# mc_pcb.net
KiCad netlist of a schematic drawn in EAGLE
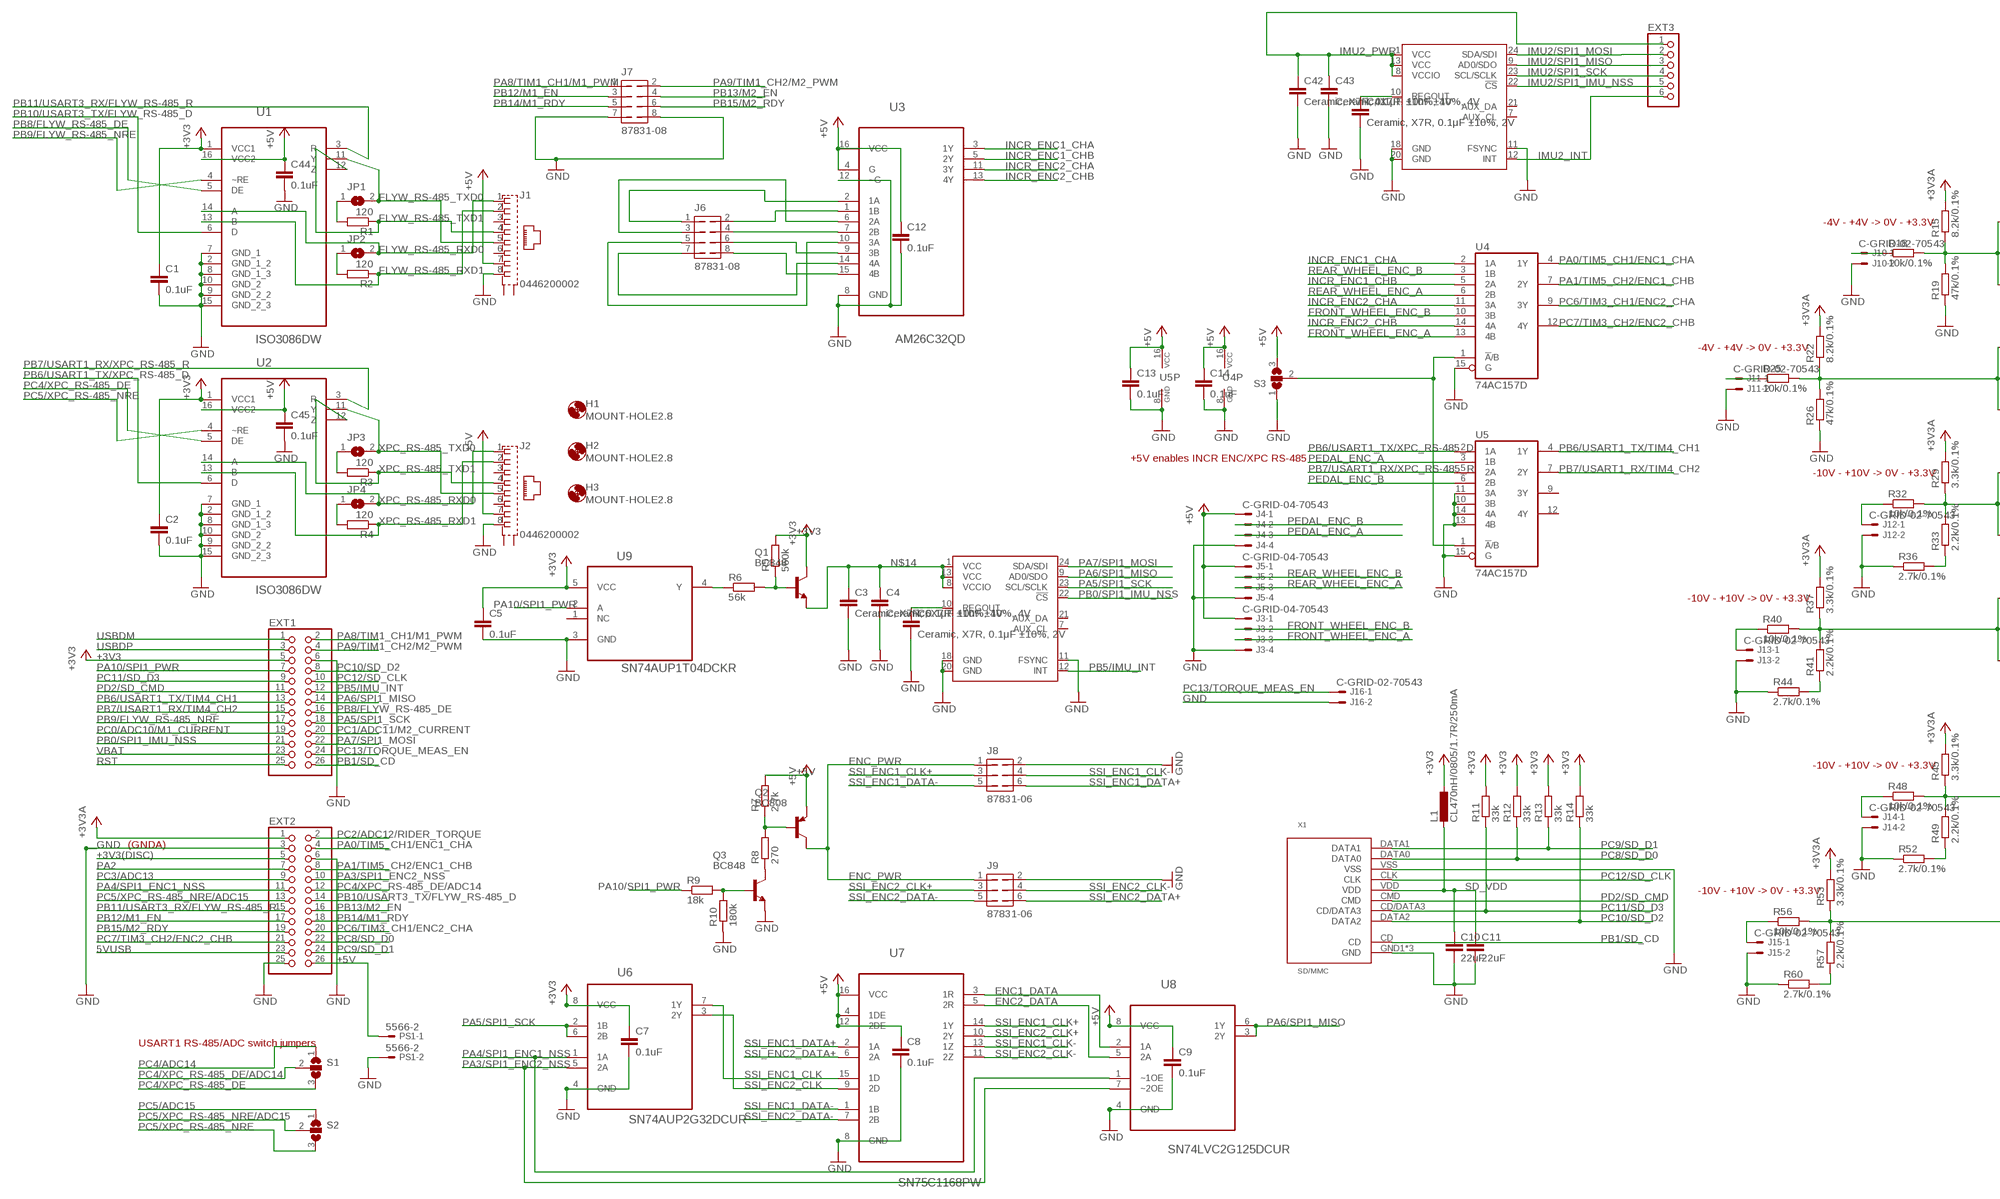
[diagram p0: schematic, sheet 1, part 1 of 2]
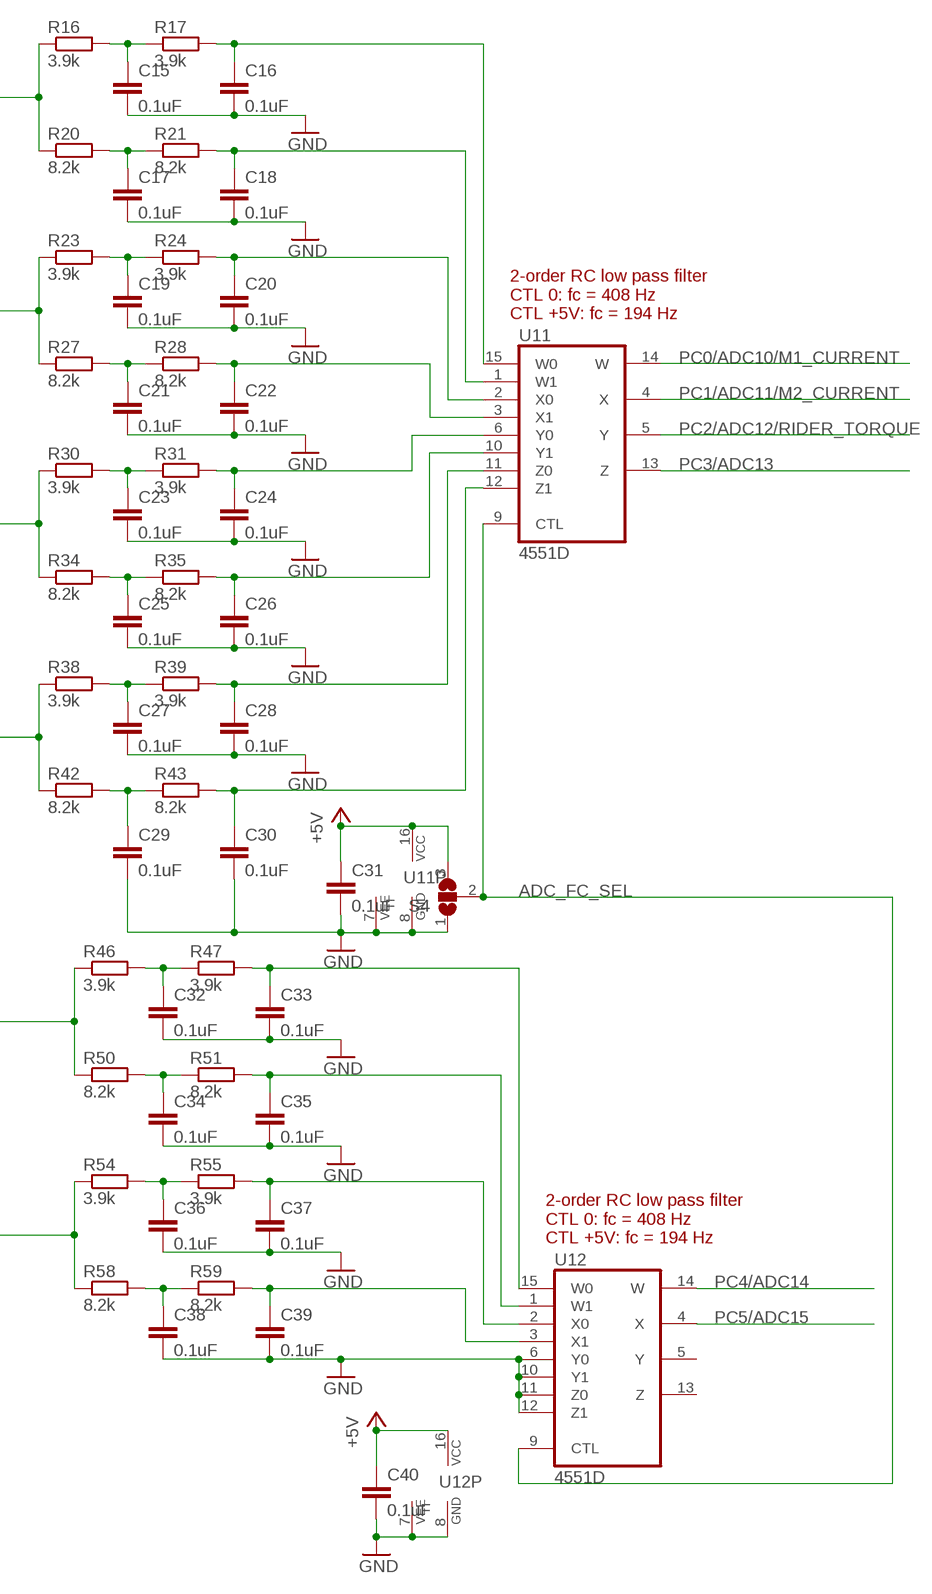
[diagram p1: schematic, sheet 1, part 2 of 2]

(export (version "E")
  (design (tool "Eeschema 10.0.6"))
  (components
    (comp (ref "C1")
      (value "0.1uF")
      (footprint "eagle-import:C0603")
      (libsource (lib "eagle-import") (part "C-EUC0603"))
    )
    (comp (ref "C2")
      (value "0.1uF")
      (footprint "eagle-import:C0603")
      (libsource (lib "eagle-import") (part "C-EUC0603"))
    )
    (comp (ref "C3")
      (value "Ceramic, X7R, 0.1μF ±10%, 4V")
      (footprint "eagle-import:C0603")
      (libsource (lib "eagle-import") (part "C-EUC0603"))
    )
    (comp (ref "C4")
      (value "Ceramic, X7R, 10nF ±10%, 4V")
      (footprint "eagle-import:C0603")
      (libsource (lib "eagle-import") (part "C-EUC0603"))
    )
    (comp (ref "C5")
      (value "0.1uF")
      (footprint "eagle-import:C0603")
      (libsource (lib "eagle-import") (part "C-EUC0603"))
    )
    (comp (ref "C6")
      (value "Ceramic, X7R, 0.1μF ±10%, 2V")
      (footprint "eagle-import:C0603")
      (libsource (lib "eagle-import") (part "C-EUC0603"))
    )
    (comp (ref "C7")
      (value "0.1uF")
      (footprint "eagle-import:C0603")
      (libsource (lib "eagle-import") (part "C-EUC0603"))
    )
    (comp (ref "C8")
      (value "0.1uF")
      (footprint "eagle-import:C0603")
      (libsource (lib "eagle-import") (part "C-EUC0603"))
    )
    (comp (ref "C9")
      (value "0.1uF")
      (footprint "eagle-import:C0603")
      (libsource (lib "eagle-import") (part "C-EUC0603"))
    )
    (comp (ref "C10")
      (value "22uF")
      (footprint "eagle-import:C0603")
      (libsource (lib "eagle-import") (part "C-EUC0603"))
    )
    (comp (ref "C11")
      (value "22uF")
      (footprint "eagle-import:C0603")
      (libsource (lib "eagle-import") (part "C-EUC0603"))
    )
    (comp (ref "C12")
      (value "0.1uF")
      (footprint "eagle-import:C0603")
      (libsource (lib "eagle-import") (part "C-EUC0603"))
    )
    (comp (ref "C13")
      (value "0.1uF")
      (footprint "eagle-import:C0603")
      (libsource (lib "eagle-import") (part "C-EUC0603"))
    )
    (comp (ref "C14")
      (value "0.1uF")
      (footprint "eagle-import:C0603")
      (libsource (lib "eagle-import") (part "C-EUC0603"))
    )
    (comp (ref "C15")
      (value "0.1uF")
      (footprint "eagle-import:C0603")
      (libsource (lib "eagle-import") (part "C-EUC0603"))
    )
    (comp (ref "C16")
      (value "0.1uF")
      (footprint "eagle-import:C0603")
      (libsource (lib "eagle-import") (part "C-EUC0603"))
    )
    (comp (ref "C17")
      (value "0.1uF")
      (footprint "eagle-import:C0603")
      (libsource (lib "eagle-import") (part "C-EUC0603"))
    )
    (comp (ref "C18")
      (value "0.1uF")
      (footprint "eagle-import:C0603")
      (libsource (lib "eagle-import") (part "C-EUC0603"))
    )
    (comp (ref "C19")
      (value "0.1uF")
      (footprint "eagle-import:C0603")
      (libsource (lib "eagle-import") (part "C-EUC0603"))
    )
    (comp (ref "C20")
      (value "0.1uF")
      (footprint "eagle-import:C0603")
      (libsource (lib "eagle-import") (part "C-EUC0603"))
    )
    (comp (ref "C21")
      (value "0.1uF")
      (footprint "eagle-import:C0603")
      (libsource (lib "eagle-import") (part "C-EUC0603"))
    )
    (comp (ref "C22")
      (value "0.1uF")
      (footprint "eagle-import:C0603")
      (libsource (lib "eagle-import") (part "C-EUC0603"))
    )
    (comp (ref "C23")
      (value "0.1uF")
      (footprint "eagle-import:C0603")
      (libsource (lib "eagle-import") (part "C-EUC0603"))
    )
    (comp (ref "C24")
      (value "0.1uF")
      (footprint "eagle-import:C0603")
      (libsource (lib "eagle-import") (part "C-EUC0603"))
    )
    (comp (ref "C25")
      (value "0.1uF")
      (footprint "eagle-import:C0603")
      (libsource (lib "eagle-import") (part "C-EUC0603"))
    )
    (comp (ref "C26")
      (value "0.1uF")
      (footprint "eagle-import:C0603")
      (libsource (lib "eagle-import") (part "C-EUC0603"))
    )
    (comp (ref "C27")
      (value "0.1uF")
      (footprint "eagle-import:C0603")
      (libsource (lib "eagle-import") (part "C-EUC0603"))
    )
    (comp (ref "C28")
      (value "0.1uF")
      (footprint "eagle-import:C0603")
      (libsource (lib "eagle-import") (part "C-EUC0603"))
    )
    (comp (ref "C29")
      (value "0.1uF")
      (footprint "eagle-import:C0603")
      (libsource (lib "eagle-import") (part "C-EUC0603"))
    )
    (comp (ref "C30")
      (value "0.1uF")
      (footprint "eagle-import:C0603")
      (libsource (lib "eagle-import") (part "C-EUC0603"))
    )
    (comp (ref "C31")
      (value "0.1uF")
      (footprint "eagle-import:C0603")
      (libsource (lib "eagle-import") (part "C-EUC0603"))
    )
    (comp (ref "C32")
      (value "0.1uF")
      (footprint "eagle-import:C0603")
      (libsource (lib "eagle-import") (part "C-EUC0603"))
    )
    (comp (ref "C33")
      (value "0.1uF")
      (footprint "eagle-import:C0603")
      (libsource (lib "eagle-import") (part "C-EUC0603"))
    )
    (comp (ref "C34")
      (value "0.1uF")
      (footprint "eagle-import:C0603")
      (libsource (lib "eagle-import") (part "C-EUC0603"))
    )
    (comp (ref "C35")
      (value "0.1uF")
      (footprint "eagle-import:C0603")
      (libsource (lib "eagle-import") (part "C-EUC0603"))
    )
    (comp (ref "C36")
      (value "0.1uF")
      (footprint "eagle-import:C0603")
      (libsource (lib "eagle-import") (part "C-EUC0603"))
    )
    (comp (ref "C37")
      (value "0.1uF")
      (footprint "eagle-import:C0603")
      (libsource (lib "eagle-import") (part "C-EUC0603"))
    )
    (comp (ref "C38")
      (value "0.1uF")
      (footprint "eagle-import:C0603")
      (libsource (lib "eagle-import") (part "C-EUC0603"))
    )
    (comp (ref "C39")
      (value "0.1uF")
      (footprint "eagle-import:C0603")
      (libsource (lib "eagle-import") (part "C-EUC0603"))
    )
    (comp (ref "C40")
      (value "0.1uF")
      (footprint "eagle-import:C0603")
      (libsource (lib "eagle-import") (part "C-EUC0603"))
    )
    (comp (ref "C41")
      (value "Ceramic, X7R, 0.1μF ±10%, 2V")
      (footprint "eagle-import:C0603")
      (libsource (lib "eagle-import") (part "C-EUC0603"))
    )
    (comp (ref "C42")
      (value "Ceramic, X7R, 0.1μF ±10%, 4V")
      (footprint "eagle-import:C0603")
      (libsource (lib "eagle-import") (part "C-EUC0603"))
    )
    (comp (ref "C43")
      (value "Ceramic, X7R, 10nF ±10%, 4V")
      (footprint "eagle-import:C0603")
      (libsource (lib "eagle-import") (part "C-EUC0603"))
    )
    (comp (ref "C44")
      (value "0.1uF")
      (footprint "eagle-import:C0603")
      (libsource (lib "eagle-import") (part "C-EUC0603"))
    )
    (comp (ref "C45")
      (value "0.1uF")
      (footprint "eagle-import:C0603")
      (libsource (lib "eagle-import") (part "C-EUC0603"))
    )
    (comp (ref "EXT1")
      (value "PINHD-2X13")
      (footprint "eagle-import:2X13")
      (libsource (lib "eagle-import") (part "PINHD-2X13"))
    )
    (comp (ref "EXT2")
      (value "PINHD-2X13")
      (footprint "eagle-import:2X13")
      (libsource (lib "eagle-import") (part "PINHD-2X13"))
    )
    (comp (ref "EXT3")
      (value "PINHD-1X6")
      (footprint "eagle-import:1X06")
      (libsource (lib "eagle-import") (part "PINHD-1X6"))
    )
    (comp (ref "H1")
      (value "MOUNT-HOLE2.8")
      (footprint "eagle-import:2,8")
      (libsource (lib "eagle-import") (part "MOUNT-HOLE2.8"))
    )
    (comp (ref "H2")
      (value "MOUNT-HOLE2.8")
      (footprint "eagle-import:2,8")
      (libsource (lib "eagle-import") (part "MOUNT-HOLE2.8"))
    )
    (comp (ref "H3")
      (value "MOUNT-HOLE2.8")
      (footprint "eagle-import:2,8")
      (libsource (lib "eagle-import") (part "MOUNT-HOLE2.8"))
    )
    (comp (ref "J1")
      (value "0446200002")
      (footprint "eagle-import:0446200002")
      (fields (field (name "MF") "MOLEX"))
      (libsource (lib "eagle-import") (part "0446200002"))
    )
    (comp (ref "J2")
      (value "0446200002")
      (footprint "eagle-import:0446200002")
      (fields (field (name "MF") "MOLEX"))
      (libsource (lib "eagle-import") (part "0446200002"))
    )
    (comp (ref "J3")
      (value "C-GRID-04-70543")
      (footprint "eagle-import:70543-04")
      (libsource (lib "eagle-import") (part "C-GRID-04-70543"))
    )
    (comp (ref "J4")
      (value "C-GRID-04-70543")
      (footprint "eagle-import:70543-04")
      (libsource (lib "eagle-import") (part "C-GRID-04-70543"))
    )
    (comp (ref "J5")
      (value "C-GRID-04-70543")
      (footprint "eagle-import:70543-04")
      (libsource (lib "eagle-import") (part "C-GRID-04-70543"))
    )
    (comp (ref "J6")
      (value "87831-08")
      (footprint "eagle-import:87831-08")
      (libsource (lib "eagle-import") (part "87831-08"))
    )
    (comp (ref "J7")
      (value "87831-08")
      (footprint "eagle-import:87831-08")
      (libsource (lib "eagle-import") (part "87831-08"))
    )
    (comp (ref "J8")
      (value "87831-06")
      (footprint "eagle-import:87831-06")
      (libsource (lib "eagle-import") (part "87831-06"))
    )
    (comp (ref "J9")
      (value "87831-06")
      (footprint "eagle-import:87831-06")
      (libsource (lib "eagle-import") (part "87831-06"))
    )
    (comp (ref "J10")
      (value "C-GRID-02-70543")
      (footprint "eagle-import:70543-02")
      (libsource (lib "eagle-import") (part "C-GRID-02-70543"))
    )
    (comp (ref "J11")
      (value "C-GRID-02-70543")
      (footprint "eagle-import:70543-02")
      (libsource (lib "eagle-import") (part "C-GRID-02-70543"))
    )
    (comp (ref "J12")
      (value "C-GRID-02-70543")
      (footprint "eagle-import:70543-02")
      (libsource (lib "eagle-import") (part "C-GRID-02-70543"))
    )
    (comp (ref "J13")
      (value "C-GRID-02-70543")
      (footprint "eagle-import:70543-02")
      (libsource (lib "eagle-import") (part "C-GRID-02-70543"))
    )
    (comp (ref "J14")
      (value "C-GRID-02-70543")
      (footprint "eagle-import:70543-02")
      (libsource (lib "eagle-import") (part "C-GRID-02-70543"))
    )
    (comp (ref "J15")
      (value "C-GRID-02-70543")
      (footprint "eagle-import:70543-02")
      (libsource (lib "eagle-import") (part "C-GRID-02-70543"))
    )
    (comp (ref "J16")
      (value "C-GRID-02-70543")
      (footprint "eagle-import:70543-02")
      (libsource (lib "eagle-import") (part "C-GRID-02-70543"))
    )
    (comp (ref "JP1") (value "SJ") (footprint "eagle-import:SJ") (libsource (lib "eagle-import") (part "SJ")))
    (comp (ref "JP2") (value "SJ") (footprint "eagle-import:SJ") (libsource (lib "eagle-import") (part "SJ")))
    (comp (ref "JP3") (value "SJ") (footprint "eagle-import:SJ") (libsource (lib "eagle-import") (part "SJ")))
    (comp (ref "JP4") (value "SJ") (footprint "eagle-import:SJ") (libsource (lib "eagle-import") (part "SJ")))
    (comp (ref "L1")
      (value "CL470nH/0805/1.7R/250mA")
      (footprint "eagle-import:L2012C")
      (libsource (lib "eagle-import") (part "L-EUL2012C"))
    )
    (comp (ref "PS1")
      (value "5566-2")
      (footprint "eagle-import:5566-2")
      (libsource (lib "eagle-import") (part "5566-2"))
    )
    (comp (ref "Q1")
      (value "BC848")
      (footprint "eagle-import:SOT23")
      (libsource (lib "eagle-import") (part "BC848"))
    )
    (comp (ref "Q2")
      (value "BC808")
      (footprint "eagle-import:SOT23-BEC")
      (libsource (lib "eagle-import") (part "-PNP-SOT23-BECBC808-16"))
    )
    (comp (ref "Q3")
      (value "BC848")
      (footprint "eagle-import:SOT23")
      (libsource (lib "eagle-import") (part "BC848"))
    )
    (comp (ref "R1")
      (value "120")
      (footprint "eagle-import:R0603")
      (libsource (lib "eagle-import") (part "R-EU_R0603"))
    )
    (comp (ref "R2")
      (value "120")
      (footprint "eagle-import:R0603")
      (libsource (lib "eagle-import") (part "R-EU_R0603"))
    )
    (comp (ref "R3")
      (value "120")
      (footprint "eagle-import:R0603")
      (libsource (lib "eagle-import") (part "R-EU_R0603"))
    )
    (comp (ref "R4")
      (value "120")
      (footprint "eagle-import:R0603")
      (libsource (lib "eagle-import") (part "R-EU_R0603"))
    )
    (comp (ref "R5")
      (value "560k")
      (footprint "eagle-import:R0603")
      (libsource (lib "eagle-import") (part "R-EU_R0603"))
    )
    (comp (ref "R6")
      (value "56k")
      (footprint "eagle-import:R0603")
      (libsource (lib "eagle-import") (part "R-EU_R0603"))
    )
    (comp (ref "R7")
      (value "2.7k")
      (footprint "eagle-import:R1210")
      (libsource (lib "eagle-import") (part "R-EU_R1210"))
    )
    (comp (ref "R8")
      (value "270")
      (footprint "eagle-import:R1210")
      (libsource (lib "eagle-import") (part "R-EU_R1210"))
    )
    (comp (ref "R9")
      (value "18k")
      (footprint "eagle-import:R0603")
      (libsource (lib "eagle-import") (part "R-EU_R0603"))
    )
    (comp (ref "R10")
      (value "180k")
      (footprint "eagle-import:R0603")
      (libsource (lib "eagle-import") (part "R-EU_R0603"))
    )
    (comp (ref "R11")
      (value "33k")
      (footprint "eagle-import:R0603")
      (libsource (lib "eagle-import") (part "R-EU_R0603"))
    )
    (comp (ref "R12")
      (value "33k")
      (footprint "eagle-import:R0603")
      (libsource (lib "eagle-import") (part "R-EU_R0603"))
    )
    (comp (ref "R13")
      (value "33k")
      (footprint "eagle-import:R0603")
      (libsource (lib "eagle-import") (part "R-EU_R0603"))
    )
    (comp (ref "R14")
      (value "33k")
      (footprint "eagle-import:R0603")
      (libsource (lib "eagle-import") (part "R-EU_R0603"))
    )
    (comp (ref "R15")
      (value "8.2k/0.1%")
      (footprint "eagle-import:R0603")
      (libsource (lib "eagle-import") (part "R-EU_R0603"))
    )
    (comp (ref "R16")
      (value "3.9k")
      (footprint "eagle-import:R0603")
      (libsource (lib "eagle-import") (part "R-EU_R0603"))
    )
    (comp (ref "R17")
      (value "3.9k")
      (footprint "eagle-import:R0603")
      (libsource (lib "eagle-import") (part "R-EU_R0603"))
    )
    (comp (ref "R18")
      (value "10k/0.1%")
      (footprint "eagle-import:R0603")
      (libsource (lib "eagle-import") (part "R-EU_R0603"))
    )
    (comp (ref "R19")
      (value "47k/0.1%")
      (footprint "eagle-import:R0603")
      (libsource (lib "eagle-import") (part "R-EU_R0603"))
    )
    (comp (ref "R20")
      (value "8.2k")
      (footprint "eagle-import:R0603")
      (libsource (lib "eagle-import") (part "R-EU_R0603"))
    )
    (comp (ref "R21")
      (value "8.2k")
      (footprint "eagle-import:R0603")
      (libsource (lib "eagle-import") (part "R-EU_R0603"))
    )
    (comp (ref "R22")
      (value "8.2k/0.1%")
      (footprint "eagle-import:R0603")
      (libsource (lib "eagle-import") (part "R-EU_R0603"))
    )
    (comp (ref "R23")
      (value "3.9k")
      (footprint "eagle-import:R0603")
      (libsource (lib "eagle-import") (part "R-EU_R0603"))
    )
    (comp (ref "R24")
      (value "3.9k")
      (footprint "eagle-import:R0603")
      (libsource (lib "eagle-import") (part "R-EU_R0603"))
    )
    (comp (ref "R25")
      (value "10k/0.1%")
      (footprint "eagle-import:R0603")
      (libsource (lib "eagle-import") (part "R-EU_R0603"))
    )
    (comp (ref "R26")
      (value "47k/0.1%")
      (footprint "eagle-import:R0603")
      (libsource (lib "eagle-import") (part "R-EU_R0603"))
    )
    (comp (ref "R27")
      (value "8.2k")
      (footprint "eagle-import:R0603")
      (libsource (lib "eagle-import") (part "R-EU_R0603"))
    )
    (comp (ref "R28")
      (value "8.2k")
      (footprint "eagle-import:R0603")
      (libsource (lib "eagle-import") (part "R-EU_R0603"))
    )
    (comp (ref "R29")
      (value "3.3k/0.1%")
      (footprint "eagle-import:R0603")
      (libsource (lib "eagle-import") (part "R-EU_R0603"))
    )
    (comp (ref "R30")
      (value "3.9k")
      (footprint "eagle-import:R0603")
      (libsource (lib "eagle-import") (part "R-EU_R0603"))
    )
    (comp (ref "R31")
      (value "3.9k")
      (footprint "eagle-import:R0603")
      (libsource (lib "eagle-import") (part "R-EU_R0603"))
    )
    (comp (ref "R32")
      (value "10k/0.1%")
      (footprint "eagle-import:R0603")
      (libsource (lib "eagle-import") (part "R-EU_R0603"))
    )
    (comp (ref "R33")
      (value "2.2k/0.1%")
      (footprint "eagle-import:R0603")
      (libsource (lib "eagle-import") (part "R-EU_R0603"))
    )
    (comp (ref "R34")
      (value "8.2k")
      (footprint "eagle-import:R0603")
      (libsource (lib "eagle-import") (part "R-EU_R0603"))
    )
    (comp (ref "R35")
      (value "8.2k")
      (footprint "eagle-import:R0603")
      (libsource (lib "eagle-import") (part "R-EU_R0603"))
    )
    (comp (ref "R36")
      (value "2.7k/0.1%")
      (footprint "eagle-import:R0603")
      (libsource (lib "eagle-import") (part "R-EU_R0603"))
    )
    (comp (ref "R37")
      (value "3.3k/0.1%")
      (footprint "eagle-import:R0603")
      (libsource (lib "eagle-import") (part "R-EU_R0603"))
    )
    (comp (ref "R38")
      (value "3.9k")
      (footprint "eagle-import:R0603")
      (libsource (lib "eagle-import") (part "R-EU_R0603"))
    )
    (comp (ref "R39")
      (value "3.9k")
      (footprint "eagle-import:R0603")
      (libsource (lib "eagle-import") (part "R-EU_R0603"))
    )
    (comp (ref "R40")
      (value "10k/0.1%")
      (footprint "eagle-import:R0603")
      (libsource (lib "eagle-import") (part "R-EU_R0603"))
    )
    (comp (ref "R41")
      (value "2.2k/0.1%")
      (footprint "eagle-import:R0603")
      (libsource (lib "eagle-import") (part "R-EU_R0603"))
    )
    (comp (ref "R42")
      (value "8.2k")
      (footprint "eagle-import:R0603")
      (libsource (lib "eagle-import") (part "R-EU_R0603"))
    )
    (comp (ref "R43")
      (value "8.2k")
      (footprint "eagle-import:R0603")
      (libsource (lib "eagle-import") (part "R-EU_R0603"))
    )
    (comp (ref "R44")
      (value "2.7k/0.1%")
      (footprint "eagle-import:R0603")
      (libsource (lib "eagle-import") (part "R-EU_R0603"))
    )
    (comp (ref "R45")
      (value "3.3k/0.1%")
      (footprint "eagle-import:R0603")
      (libsource (lib "eagle-import") (part "R-EU_R0603"))
    )
    (comp (ref "R46")
      (value "3.9k")
      (footprint "eagle-import:R0603")
      (libsource (lib "eagle-import") (part "R-EU_R0603"))
    )
    (comp (ref "R47")
      (value "3.9k")
      (footprint "eagle-import:R0603")
      (libsource (lib "eagle-import") (part "R-EU_R0603"))
    )
    (comp (ref "R48")
      (value "10k/0.1%")
      (footprint "eagle-import:R0603")
      (libsource (lib "eagle-import") (part "R-EU_R0603"))
    )
    (comp (ref "R49")
      (value "2.2k/0.1%")
      (footprint "eagle-import:R0603")
      (libsource (lib "eagle-import") (part "R-EU_R0603"))
    )
    (comp (ref "R50")
      (value "8.2k")
      (footprint "eagle-import:R0603")
      (libsource (lib "eagle-import") (part "R-EU_R0603"))
    )
    (comp (ref "R51")
      (value "8.2k")
      (footprint "eagle-import:R0603")
      (libsource (lib "eagle-import") (part "R-EU_R0603"))
    )
    (comp (ref "R52")
      (value "2.7k/0.1%")
      (footprint "eagle-import:R0603")
      (libsource (lib "eagle-import") (part "R-EU_R0603"))
    )
    (comp (ref "R53")
      (value "3.3k/0.1%")
      (footprint "eagle-import:R0603")
      (libsource (lib "eagle-import") (part "R-EU_R0603"))
    )
    (comp (ref "R54")
      (value "3.9k")
      (footprint "eagle-import:R0603")
      (libsource (lib "eagle-import") (part "R-EU_R0603"))
    )
    (comp (ref "R55")
      (value "3.9k")
      (footprint "eagle-import:R0603")
      (libsource (lib "eagle-import") (part "R-EU_R0603"))
    )
    (comp (ref "R56")
      (value "10k/0.1%")
      (footprint "eagle-import:R0603")
      (libsource (lib "eagle-import") (part "R-EU_R0603"))
    )
    (comp (ref "R57")
      (value "2.2k/0.1%")
      (footprint "eagle-import:R0603")
      (libsource (lib "eagle-import") (part "R-EU_R0603"))
    )
    (comp (ref "R58")
      (value "8.2k")
      (footprint "eagle-import:R0603")
      (libsource (lib "eagle-import") (part "R-EU_R0603"))
    )
    (comp (ref "R59")
      (value "8.2k")
      (footprint "eagle-import:R0603")
      (libsource (lib "eagle-import") (part "R-EU_R0603"))
    )
    (comp (ref "R60")
      (value "2.7k/0.1%")
      (footprint "eagle-import:R0603")
      (libsource (lib "eagle-import") (part "R-EU_R0603"))
    )
    (comp (ref "S1")
      (value "SJ2W")
      (footprint "eagle-import:SJ_2")
      (libsource (lib "eagle-import") (part "SJ2W"))
    )
    (comp (ref "S2")
      (value "SJ2W")
      (footprint "eagle-import:SJ_2")
      (libsource (lib "eagle-import") (part "SJ2W"))
    )
    (comp (ref "S3")
      (value "SJ2W")
      (footprint "eagle-import:SJ_2")
      (libsource (lib "eagle-import") (part "SJ2W"))
    )
    (comp (ref "S4")
      (value "SJ2W")
      (footprint "eagle-import:SJ_2")
      (libsource (lib "eagle-import") (part "SJ2W"))
    )
    (comp (ref "U1")
      (value "ISO3086DW")
      (footprint "eagle-import:SOIC127P1030X265-16N")
      (fields (field (name "MPN") "ISO3080DW"))
      (libsource (lib "eagle-import") (part "ISO3086DW"))
    )
    (comp (ref "U2")
      (value "ISO3086DW")
      (footprint "eagle-import:SOIC127P1030X265-16N")
      (fields (field (name "MPN") "ISO3080DW"))
      (libsource (lib "eagle-import") (part "ISO3086DW"))
    )
    (comp (ref "U3")
      (value "AM26C32QD")
      (footprint "eagle-import:SOIC127P600X175-16N")
      (libsource (lib "eagle-import") (part "AM26C32QD"))
    )
    (comp (ref "U4")
      (value "74AC157D")
      (footprint "eagle-import:SO16")
      (libsource (lib "eagle-import") (part "74157DAC"))
    )
    (comp (ref "U5")
      (value "74AC157D")
      (footprint "eagle-import:SO16")
      (libsource (lib "eagle-import") (part "74157DAC"))
    )
    (comp (ref "U6")
      (value "SN74AUP2G32DCUR")
      (footprint "eagle-import:SOP50P310X90-8N")
      (libsource (lib "eagle-import") (part "SN74AUP2G32DCUR"))
    )
    (comp (ref "U7")
      (value "SN75C1168PW")
      (footprint "eagle-import:SOP65P640X120-16N")
      (libsource (lib "eagle-import") (part "SN75C1168PW"))
    )
    (comp (ref "U8")
      (value "SN74LVC2G125DCUR")
      (footprint "eagle-import:SOP50P310X90-8N")
      (libsource (lib "eagle-import") (part "SN74LVC2G125DCUR"))
    )
    (comp (ref "U9")
      (value "SN74AUP1T04DCKR")
      (footprint "eagle-import:SOT65P210X110-5N")
      (libsource (lib "eagle-import") (part "SN74AUP1T04DCKR"))
    )
    (comp (ref "U10")
      (value "MPU-9250")
      (footprint "eagle-import:QFN24-SMALL")
      (libsource (lib "eagle-import") (part "MPU-9250"))
    )
    (comp (ref "U11")
      (value "4551D")
      (footprint "eagle-import:SO16")
      (libsource (lib "eagle-import") (part "4551D"))
    )
    (comp (ref "U12")
      (value "4551D")
      (footprint "eagle-import:SO16")
      (libsource (lib "eagle-import") (part "4551D"))
    )
    (comp (ref "U13")
      (value "MPU-9250")
      (footprint "eagle-import:QFN24-SMALL")
      (libsource (lib "eagle-import") (part "MPU-9250"))
    )
    (comp (ref "X1")
      (value "10100660")
      (footprint "eagle-import:-68-6")
      (libsource (lib "eagle-import") (part "10100660"))
    )
  )
  (nets
    (net (code "1") (name "+3V3") (class "Default")
      (node (ref "C1") (pin "1") (pinfunction "1_1") (pintype "passive"))
      (node (ref "C2") (pin "1") (pinfunction "1_1") (pintype "passive"))
      (node (ref "C5") (pin "1") (pinfunction "1_1") (pintype "passive"))
      (node (ref "C7") (pin "1") (pinfunction "1_1") (pintype "passive"))
      (node (ref "EXT1") (pin "5") (pinfunction "5_5") (pintype "passive"))
      (node (ref "L1") (pin "1") (pinfunction "1_1") (pintype "passive"))
      (node (ref "Q1") (pin "3") (pinfunction "C_3") (pintype "passive"))
      (node (ref "R11") (pin "2") (pinfunction "2_2") (pintype "passive"))
      (node (ref "R12") (pin "2") (pinfunction "2_2") (pintype "passive"))
      (node (ref "R13") (pin "2") (pinfunction "2_2") (pintype "passive"))
      (node (ref "R14") (pin "2") (pinfunction "2_2") (pintype "passive"))
      (node (ref "R5") (pin "2") (pinfunction "2_2") (pintype "passive"))
      (node (ref "U1") (pin "1") (pinfunction "VCC1_1") (pintype "power_in"))
      (node (ref "U2") (pin "1") (pinfunction "VCC1_1") (pintype "power_in"))
      (node (ref "U6") (pin "8") (pinfunction "VCC_8") (pintype "power_in"))
      (node (ref "U9") (pin "5") (pinfunction "VCC_5") (pintype "power_in"))
    )
    (net (code "2") (name "+3V3A") (class "Default")
      (node (ref "EXT2") (pin "1") (pinfunction "1_1") (pintype "passive"))
      (node (ref "R15") (pin "2") (pinfunction "2_2") (pintype "passive"))
      (node (ref "R22") (pin "2") (pinfunction "2_2") (pintype "passive"))
      (node (ref "R29") (pin "2") (pinfunction "2_2") (pintype "passive"))
      (node (ref "R37") (pin "2") (pinfunction "2_2") (pintype "passive"))
      (node (ref "R45") (pin "2") (pinfunction "2_2") (pintype "passive"))
      (node (ref "R53") (pin "2") (pinfunction "2_2") (pintype "passive"))
    )
    (net (code "3") (name "+5V") (class "Default")
      (node (ref "C12") (pin "1") (pinfunction "1_1") (pintype "passive"))
      (node (ref "C13") (pin "1") (pinfunction "1_1") (pintype "passive"))
      (node (ref "C14") (pin "1") (pinfunction "1_1") (pintype "passive"))
      (node (ref "C31") (pin "1") (pinfunction "1_1") (pintype "passive"))
      (node (ref "C40") (pin "1") (pinfunction "1_1") (pintype "passive"))
      (node (ref "C44") (pin "1") (pinfunction "1_1") (pintype "passive"))
      (node (ref "C45") (pin "1") (pinfunction "1_1") (pintype "passive"))
      (node (ref "C8") (pin "1") (pinfunction "1_1") (pintype "passive"))
      (node (ref "C9") (pin "1") (pinfunction "1_1") (pintype "passive"))
      (node (ref "EXT2") (pin "26") (pinfunction "26_26") (pintype "passive"))
      (node (ref "J1") (pin "7") (pinfunction "7_7") (pintype "passive"))
      (node (ref "J2") (pin "7") (pinfunction "7_7") (pintype "passive"))
      (node (ref "J3") (pin "1") (pinfunction "S_1") (pintype "passive"))
      (node (ref "J4") (pin "1") (pinfunction "S_1") (pintype "passive"))
      (node (ref "J5") (pin "1") (pinfunction "S_1") (pintype "passive"))
      (node (ref "PS1") (pin "1") (pinfunction "S_1") (pintype "passive"))
      (node (ref "Q2") (pin "E") (pinfunction "E_E") (pintype "passive"))
      (node (ref "R7") (pin "2") (pinfunction "2_2") (pintype "passive"))
      (node (ref "S3") (pin "3") (pinfunction "3_3") (pintype "passive"))
      (node (ref "S4") (pin "3") (pinfunction "3_3") (pintype "passive"))
      (node (ref "U1") (pin "16") (pinfunction "VCC2_16") (pintype "power_in"))
      (node (ref "U11") (pin "16") (pinfunction "VCC_16") (pintype "power_in"))
      (node (ref "U12") (pin "16") (pinfunction "VCC_16") (pintype "power_in"))
      (node (ref "U2") (pin "16") (pinfunction "VCC2_16") (pintype "power_in"))
      (node (ref "U3") (pin "16") (pinfunction "VCC_16") (pintype "power_in"))
      (node (ref "U3") (pin "4") (pinfunction "G_4") (pintype "input"))
      (node (ref "U4") (pin "16") (pinfunction "VCC_16") (pintype "power_in"))
      (node (ref "U5") (pin "16") (pinfunction "VCC_16") (pintype "power_in"))
      (node (ref "U7") (pin "12") (pinfunction "2DE_12") (pintype "input"))
      (node (ref "U7") (pin "16") (pinfunction "VCC_16") (pintype "power_in"))
      (node (ref "U7") (pin "4") (pinfunction "1DE_4") (pintype "input"))
      (node (ref "U8") (pin "8") (pinfunction "VCC_8") (pintype "power_in"))
    )
    (net (code "4") (name "/+3V3(DISC)") (class "Default")
      (node (ref "EXT2") (pin "5") (pinfunction "5_5") (pintype "passive"))
    )
    (net (code "5") (name "/5VUSB") (class "Default")
      (node (ref "EXT2") (pin "23") (pinfunction "23_23") (pintype "passive"))
    )
    (net (code "6") (name "/ADC_FC_SEL") (class "Default")
      (node (ref "S4") (pin "2") (pinfunction "2_2") (pintype "passive"))
      (node (ref "U11") (pin "9") (pinfunction "CTL_9") (pintype "input"))
      (node (ref "U12") (pin "9") (pinfunction "CTL_9") (pintype "input"))
    )
    (net (code "7") (name "/ENC1_DATA") (class "Default")
      (node (ref "U7") (pin "3") (pinfunction "1R_3") (pintype "output"))
      (node (ref "U8") (pin "2") (pinfunction "1A_2") (pintype "input"))
    )
    (net (code "8") (name "/ENC2_DATA") (class "Default")
      (node (ref "U7") (pin "5") (pinfunction "2R_5") (pintype "output"))
      (node (ref "U8") (pin "5") (pinfunction "2A_5") (pintype "input"))
    )
    (net (code "9") (name "/ENC_PWR") (class "Default")
      (node (ref "J8") (pin "1") (pinfunction "1_1") (pintype "passive"))
      (node (ref "J9") (pin "1") (pinfunction "1_1") (pintype "passive"))
      (node (ref "Q2") (pin "C") (pinfunction "C_C") (pintype "passive"))
    )
    (net (code "10") (name "/FLYW_RS-485_RXD0") (class "Default")
      (node (ref "J1") (pin "1") (pinfunction "1_1") (pintype "passive"))
      (node (ref "JP2") (pin "2") (pinfunction "2_2") (pintype "passive"))
      (node (ref "U1") (pin "14") (pinfunction "A_14") (pintype "input"))
    )
    (net (code "11") (name "/FLYW_RS-485_RXD1") (class "Default")
      (node (ref "J1") (pin "2") (pinfunction "2_2") (pintype "passive"))
      (node (ref "R2") (pin "1") (pinfunction "1_1") (pintype "passive"))
      (node (ref "U1") (pin "13") (pinfunction "B_13") (pintype "input"))
    )
    (net (code "12") (name "/FLYW_RS-485_TXD0") (class "Default")
      (node (ref "J1") (pin "5") (pinfunction "5_5") (pintype "passive"))
      (node (ref "JP1") (pin "2") (pinfunction "2_2") (pintype "passive"))
      (node (ref "U1") (pin "11") (pinfunction "Y_11") (pintype "output"))
    )
    (net (code "13") (name "/FLYW_RS-485_TXD1") (class "Default")
      (node (ref "J1") (pin "4") (pinfunction "4_4") (pintype "passive"))
      (node (ref "R1") (pin "1") (pinfunction "1_1") (pintype "passive"))
      (node (ref "U1") (pin "12") (pinfunction "Z_12") (pintype "output"))
    )
    (net (code "14") (name "/FRONT_WHEEL_ENC_A") (class "Default")
      (node (ref "J3") (pin "3") (pinfunction "S_3") (pintype "passive"))
      (node (ref "U4") (pin "13") (pinfunction "4B_13") (pintype "input"))
    )
    (net (code "15") (name "/FRONT_WHEEL_ENC_B") (class "Default")
      (node (ref "J3") (pin "2") (pinfunction "S_2") (pintype "passive"))
      (node (ref "U4") (pin "10") (pinfunction "3B_10") (pintype "input"))
    )
    (net (code "16") (name "/IMU2_INT") (class "Default")
      (node (ref "EXT3") (pin "6") (pinfunction "6_6") (pintype "passive"))
      (node (ref "U13") (pin "12") (pinfunction "INT_12") (pintype "output"))
    )
    (net (code "17") (name "/IMU2_PWR") (class "Default")
      (node (ref "C42") (pin "1") (pinfunction "1_1") (pintype "passive"))
      (node (ref "C43") (pin "1") (pinfunction "1_1") (pintype "passive"))
      (node (ref "EXT3") (pin "1") (pinfunction "1_1") (pintype "passive"))
      (node (ref "U13") (pin "1") (pinfunction "VCC_1") (pintype "power_in"))
      (node (ref "U13") (pin "13") (pinfunction "VCC_13") (pintype "power_in"))
      (node (ref "U13") (pin "8") (pinfunction "VCCIO_8") (pintype "power_in"))
    )
    (net (code "18") (name "/IMU2{slash}SPI1_IMU_NSS") (class "Default")
      (node (ref "EXT3") (pin "5") (pinfunction "5_5") (pintype "passive"))
      (node (ref "U13") (pin "22") (pinfunction "~{CS}_22") (pintype "input"))
    )
    (net (code "19") (name "/IMU2{slash}SPI1_MISO") (class "Default")
      (node (ref "EXT3") (pin "3") (pinfunction "3_3") (pintype "passive"))
      (node (ref "U13") (pin "9") (pinfunction "AD0/SDO_9") (pintype "input"))
    )
    (net (code "20") (name "/IMU2{slash}SPI1_MOSI") (class "Default")
      (node (ref "EXT3") (pin "2") (pinfunction "2_2") (pintype "passive"))
      (node (ref "U13") (pin "24") (pinfunction "SDA/SDI_24") (pintype "output"))
    )
    (net (code "21") (name "/IMU2{slash}SPI1_SCK") (class "Default")
      (node (ref "EXT3") (pin "4") (pinfunction "4_4") (pintype "passive"))
      (node (ref "U13") (pin "23") (pinfunction "SCL/SCLK_23") (pintype "bidirectional"))
    )
    (net (code "22") (name "/INCR_ENC1_CHA") (class "Default")
      (node (ref "U3") (pin "3") (pinfunction "1Y_3") (pintype "output"))
      (node (ref "U4") (pin "2") (pinfunction "1A_2") (pintype "input"))
    )
    (net (code "23") (name "/INCR_ENC1_CHB") (class "Default")
      (node (ref "U3") (pin "5") (pinfunction "2Y_5") (pintype "output"))
      (node (ref "U4") (pin "5") (pinfunction "2A_5") (pintype "input"))
    )
    (net (code "24") (name "/INCR_ENC2_CHA") (class "Default")
      (node (ref "U3") (pin "11") (pinfunction "3Y_11") (pintype "output"))
      (node (ref "U4") (pin "11") (pinfunction "3A_11") (pintype "input"))
    )
    (net (code "25") (name "/INCR_ENC2_CHB") (class "Default")
      (node (ref "U3") (pin "13") (pinfunction "4Y_13") (pintype "output"))
      (node (ref "U4") (pin "14") (pinfunction "4A_14") (pintype "input"))
    )
    (net (code "26") (name "/N$14") (class "Default")
      (node (ref "C3") (pin "1") (pinfunction "1_1") (pintype "passive"))
      (node (ref "C4") (pin "1") (pinfunction "1_1") (pintype "passive"))
      (node (ref "Q1") (pin "2") (pinfunction "E_2") (pintype "passive"))
      (node (ref "U10") (pin "1") (pinfunction "VCC_1") (pintype "power_in"))
      (node (ref "U10") (pin "13") (pinfunction "VCC_13") (pintype "power_in"))
      (node (ref "U10") (pin "8") (pinfunction "VCCIO_8") (pintype "power_in"))
    )
    (net (code "27") (name "/PA0{slash}TIM5_CH1{slash}ENC1_CHA") (class "Default")
      (node (ref "EXT2") (pin "4") (pinfunction "4_4") (pintype "passive"))
      (node (ref "U4") (pin "4") (pinfunction "1Y_4") (pintype "output"))
    )
    (net (code "28") (name "/PA1{slash}TIM5_CH2{slash}ENC1_CHB") (class "Default")
      (node (ref "EXT2") (pin "8") (pinfunction "8_8") (pintype "passive"))
      (node (ref "U4") (pin "7") (pinfunction "2Y_7") (pintype "output"))
    )
    (net (code "29") (name "/PA2") (class "Default")
      (node (ref "EXT2") (pin "7") (pinfunction "7_7") (pintype "passive"))
    )
    (net (code "30") (name "/PA3{slash}SPI1_ENC2_NSS") (class "Default")
      (node (ref "EXT2") (pin "10") (pinfunction "10_10") (pintype "passive"))
      (node (ref "U6") (pin "5") (pinfunction "2A_5") (pintype "input"))
      (node (ref "U8") (pin "7") (pinfunction "~{2OE}_7") (pintype "input"))
    )
    (net (code "31") (name "/PA4{slash}SPI1_ENC1_NSS") (class "Default")
      (node (ref "EXT2") (pin "11") (pinfunction "11_11") (pintype "passive"))
      (node (ref "U6") (pin "1") (pinfunction "1A_1") (pintype "input"))
      (node (ref "U8") (pin "1") (pinfunction "~{1OE}_1") (pintype "input"))
    )
    (net (code "32") (name "/PA5{slash}SPI1_SCK") (class "Default")
      (node (ref "EXT1") (pin "18") (pinfunction "18_18") (pintype "passive"))
      (node (ref "U10") (pin "23") (pinfunction "SCL/SCLK_23") (pintype "bidirectional"))
      (node (ref "U6") (pin "2") (pinfunction "1B_2") (pintype "input"))
      (node (ref "U6") (pin "6") (pinfunction "2B_6") (pintype "input"))
    )
    (net (code "33") (name "/PA6{slash}SPI1_MISO") (class "Default")
      (node (ref "EXT1") (pin "14") (pinfunction "14_14") (pintype "passive"))
      (node (ref "U10") (pin "9") (pinfunction "AD0/SDO_9") (pintype "input"))
      (node (ref "U8") (pin "3") (pinfunction "2Y_3") (pintype "output"))
      (node (ref "U8") (pin "6") (pinfunction "1Y_6") (pintype "output"))
    )
    (net (code "34") (name "/PA7{slash}SPI1_MOSI") (class "Default")
      (node (ref "EXT1") (pin "22") (pinfunction "22_22") (pintype "passive"))
      (node (ref "U10") (pin "24") (pinfunction "SDA/SDI_24") (pintype "output"))
    )
    (net (code "35") (name "/PA8{slash}TIM1_CH1{slash}M1_PWM") (class "Default")
      (node (ref "EXT1") (pin "2") (pinfunction "2_2") (pintype "passive"))
      (node (ref "J7") (pin "1") (pinfunction "1_1") (pintype "passive"))
    )
    (net (code "36") (name "/PA9{slash}TIM1_CH2{slash}M2_PWM") (class "Default")
      (node (ref "EXT1") (pin "4") (pinfunction "4_4") (pintype "passive"))
      (node (ref "J7") (pin "2") (pinfunction "2_2") (pintype "passive"))
    )
    (net (code "37") (name "/PA10{slash}SPI1_PWR") (class "Default")
      (node (ref "EXT1") (pin "7") (pinfunction "7_7") (pintype "passive"))
      (node (ref "R9") (pin "1") (pinfunction "1_1") (pintype "passive"))
      (node (ref "U9") (pin "2") (pinfunction "A_2") (pintype "input"))
    )
    (net (code "38") (name "/PB0{slash}SPI1_IMU_NSS") (class "Default")
      (node (ref "EXT1") (pin "21") (pinfunction "21_21") (pintype "passive"))
      (node (ref "U10") (pin "22") (pinfunction "~{CS}_22") (pintype "input"))
    )
    (net (code "39") (name "/PB1{slash}SD_CD") (class "Default")
      (node (ref "EXT1") (pin "26") (pinfunction "26_26") (pintype "passive"))
      (node (ref "X1") (pin "CD") (pinfunction "CD_CD") (pintype "passive"))
    )
    (net (code "40") (name "/PB5{slash}IMU_INT") (class "Default")
      (node (ref "EXT1") (pin "12") (pinfunction "12_12") (pintype "passive"))
      (node (ref "U10") (pin "12") (pinfunction "INT_12") (pintype "output"))
    )
    (net (code "41") (name "/PB6{slash}USART1_TX{slash}TIM4_CH1") (class "Default")
      (node (ref "EXT1") (pin "13") (pinfunction "13_13") (pintype "passive"))
      (node (ref "U5") (pin "4") (pinfunction "1Y_4") (pintype "output"))
    )
    (net (code "42") (name "/PB6{slash}USART1_TX{slash}XPC_RS-485_D") (class "Default")
      (node (ref "U2") (pin "6") (pinfunction "D_6") (pintype "input"))
      (node (ref "U5") (pin "2") (pinfunction "1A_2") (pintype "input"))
    )
    (net (code "43") (name "/PB7{slash}USART1_RX{slash}TIM4_CH2") (class "Default")
      (node (ref "EXT1") (pin "15") (pinfunction "15_15") (pintype "passive"))
      (node (ref "U5") (pin "7") (pinfunction "2Y_7") (pintype "output"))
    )
    (net (code "44") (name "/PB7{slash}USART1_RX{slash}XPC_RS-485_R") (class "Default")
      (node (ref "U2") (pin "3") (pinfunction "R_3") (pintype "output"))
      (node (ref "U5") (pin "5") (pinfunction "2A_5") (pintype "input"))
    )
    (net (code "45") (name "/PB8{slash}FLYW_RS-485_DE") (class "Default")
      (node (ref "EXT1") (pin "16") (pinfunction "16_16") (pintype "passive"))
      (node (ref "U1") (pin "5") (pinfunction "DE_5") (pintype "input"))
    )
    (net (code "46") (name "/PB9{slash}FLYW_RS-485_NRE") (class "Default")
      (node (ref "EXT1") (pin "17") (pinfunction "17_17") (pintype "passive"))
      (node (ref "U1") (pin "4") (pinfunction "~{RE}_4") (pintype "input"))
    )
    (net (code "47") (name "/PB10{slash}USART3_TX{slash}FLYW_RS-485_D") (class "Default")
      (node (ref "EXT2") (pin "14") (pinfunction "14_14") (pintype "passive"))
      (node (ref "U1") (pin "6") (pinfunction "D_6") (pintype "input"))
    )
    (net (code "48") (name "/PB11{slash}USART3_RX{slash}FLYW_RS-485_R") (class "Default")
      (node (ref "EXT2") (pin "15") (pinfunction "15_15") (pintype "passive"))
      (node (ref "U1") (pin "3") (pinfunction "R_3") (pintype "output"))
    )
    (net (code "49") (name "/PB12{slash}M1_EN") (class "Default")
      (node (ref "EXT2") (pin "17") (pinfunction "17_17") (pintype "passive"))
      (node (ref "J7") (pin "3") (pinfunction "3_3") (pintype "passive"))
    )
    (net (code "50") (name "/PB13{slash}M2_EN") (class "Default")
      (node (ref "EXT2") (pin "16") (pinfunction "16_16") (pintype "passive"))
      (node (ref "J7") (pin "4") (pinfunction "4_4") (pintype "passive"))
    )
    (net (code "51") (name "/PB14{slash}M1_RDY") (class "Default")
      (node (ref "EXT2") (pin "18") (pinfunction "18_18") (pintype "passive"))
      (node (ref "J7") (pin "5") (pinfunction "5_5") (pintype "passive"))
    )
    (net (code "52") (name "/PB15{slash}M2_RDY") (class "Default")
      (node (ref "EXT2") (pin "19") (pinfunction "19_19") (pintype "passive"))
      (node (ref "J7") (pin "6") (pinfunction "6_6") (pintype "passive"))
    )
    (net (code "53") (name "/PC0{slash}ADC10{slash}M1_CURRENT") (class "Default")
      (node (ref "EXT1") (pin "19") (pinfunction "19_19") (pintype "passive"))
      (node (ref "U11") (pin "14") (pinfunction "W_14") (pintype "bidirectional"))
    )
    (net (code "54") (name "/PC1{slash}ADC11{slash}M2_CURRENT") (class "Default")
      (node (ref "EXT1") (pin "20") (pinfunction "20_20") (pintype "passive"))
      (node (ref "U11") (pin "4") (pinfunction "X_4") (pintype "bidirectional"))
    )
    (net (code "55") (name "/PC2{slash}ADC12{slash}RIDER_TORQUE") (class "Default")
      (node (ref "EXT2") (pin "2") (pinfunction "2_2") (pintype "passive"))
      (node (ref "U11") (pin "5") (pinfunction "Y_5") (pintype "bidirectional"))
    )
    (net (code "56") (name "/PC3{slash}ADC13") (class "Default")
      (node (ref "EXT2") (pin "9") (pinfunction "9_9") (pintype "passive"))
      (node (ref "U11") (pin "13") (pinfunction "Z_13") (pintype "bidirectional"))
    )
    (net (code "57") (name "/PC4{slash}ADC14") (class "Default")
      (node (ref "S1") (pin "1") (pinfunction "1_1") (pintype "passive"))
      (node (ref "U12") (pin "14") (pinfunction "W_14") (pintype "bidirectional"))
    )
    (net (code "58") (name "/PC4{slash}XPC_RS-485_DE") (class "Default")
      (node (ref "S1") (pin "3") (pinfunction "3_3") (pintype "passive"))
      (node (ref "U2") (pin "5") (pinfunction "DE_5") (pintype "input"))
    )
    (net (code "59") (name "/PC4{slash}XPC_RS-485_DE{slash}ADC14") (class "Default")
      (node (ref "EXT2") (pin "12") (pinfunction "12_12") (pintype "passive"))
      (node (ref "S1") (pin "2") (pinfunction "2_2") (pintype "passive"))
    )
    (net (code "60") (name "/PC5{slash}ADC15") (class "Default")
      (node (ref "S2") (pin "1") (pinfunction "1_1") (pintype "passive"))
      (node (ref "U12") (pin "4") (pinfunction "X_4") (pintype "bidirectional"))
    )
    (net (code "61") (name "/PC5{slash}XPC_RS-485_NRE") (class "Default")
      (node (ref "S2") (pin "3") (pinfunction "3_3") (pintype "passive"))
      (node (ref "U2") (pin "4") (pinfunction "~{RE}_4") (pintype "input"))
    )
    (net (code "62") (name "/PC5{slash}XPC_RS-485_NRE{slash}ADC15") (class "Default")
      (node (ref "EXT2") (pin "13") (pinfunction "13_13") (pintype "passive"))
      (node (ref "S2") (pin "2") (pinfunction "2_2") (pintype "passive"))
    )
    (net (code "63") (name "/PC6{slash}TIM3_CH1{slash}ENC2_CHA") (class "Default")
      (node (ref "EXT2") (pin "20") (pinfunction "20_20") (pintype "passive"))
      (node (ref "U4") (pin "9") (pinfunction "3Y_9") (pintype "output"))
    )
    (net (code "64") (name "/PC7{slash}TIM3_CH2{slash}ENC2_CHB") (class "Default")
      (node (ref "EXT2") (pin "21") (pinfunction "21_21") (pintype "passive"))
      (node (ref "U4") (pin "12") (pinfunction "4Y_12") (pintype "output"))
    )
    (net (code "65") (name "/PC8{slash}SD_D0") (class "Default")
      (node (ref "EXT2") (pin "22") (pinfunction "22_22") (pintype "passive"))
      (node (ref "R12") (pin "1") (pinfunction "1_1") (pintype "passive"))
      (node (ref "X1") (pin "DATA0") (pinfunction "DATA0_DATA0") (pintype "passive"))
    )
    (net (code "66") (name "/PC9{slash}SD_D1") (class "Default")
      (node (ref "EXT2") (pin "24") (pinfunction "24_24") (pintype "passive"))
      (node (ref "R13") (pin "1") (pinfunction "1_1") (pintype "passive"))
      (node (ref "X1") (pin "DATA1") (pinfunction "DATA1_DATA1") (pintype "passive"))
    )
    (net (code "67") (name "/PC10{slash}SD_D2") (class "Default")
      (node (ref "EXT1") (pin "8") (pinfunction "8_8") (pintype "passive"))
      (node (ref "R14") (pin "1") (pinfunction "1_1") (pintype "passive"))
      (node (ref "X1") (pin "DATA2") (pinfunction "DATA2_DATA2") (pintype "passive"))
    )
    (net (code "68") (name "/PC11{slash}SD_D3") (class "Default")
      (node (ref "EXT1") (pin "9") (pinfunction "9_9") (pintype "passive"))
      (node (ref "R11") (pin "1") (pinfunction "1_1") (pintype "passive"))
      (node (ref "X1") (pin "CD/DATA3") (pinfunction "CD/DATA3_CD/DATA3") (pintype "passive"))
    )
    (net (code "69") (name "/PC12{slash}SD_CLK") (class "Default")
      (node (ref "EXT1") (pin "10") (pinfunction "10_10") (pintype "passive"))
      (node (ref "X1") (pin "CLK") (pinfunction "CLK_CLK") (pintype "passive"))
    )
    (net (code "70") (name "/PC13{slash}TORQUE_MEAS_EN") (class "Default")
      (node (ref "EXT1") (pin "24") (pinfunction "24_24") (pintype "passive"))
      (node (ref "J16") (pin "1") (pinfunction "S_1") (pintype "passive"))
    )
    (net (code "71") (name "/PD2{slash}SD_CMD") (class "Default")
      (node (ref "EXT1") (pin "11") (pinfunction "11_11") (pintype "passive"))
      (node (ref "X1") (pin "CMD") (pinfunction "CMD_CMD") (pintype "passive"))
    )
    (net (code "72") (name "/PEDAL_ENC_A") (class "Default")
      (node (ref "J4") (pin "3") (pinfunction "S_3") (pintype "passive"))
      (node (ref "U5") (pin "3") (pinfunction "1B_3") (pintype "input"))
    )
    (net (code "73") (name "/PEDAL_ENC_B") (class "Default")
      (node (ref "J4") (pin "2") (pinfunction "S_2") (pintype "passive"))
      (node (ref "U5") (pin "6") (pinfunction "2B_6") (pintype "input"))
    )
    (net (code "74") (name "/REAR_WHEEL_ENC_A") (class "Default")
      (node (ref "J5") (pin "3") (pinfunction "S_3") (pintype "passive"))
      (node (ref "U4") (pin "6") (pinfunction "2B_6") (pintype "input"))
    )
    (net (code "75") (name "/REAR_WHEEL_ENC_B") (class "Default")
      (node (ref "J5") (pin "2") (pinfunction "S_2") (pintype "passive"))
      (node (ref "U4") (pin "3") (pinfunction "1B_3") (pintype "input"))
    )
    (net (code "76") (name "/RST") (class "Default")
      (node (ref "EXT1") (pin "25") (pinfunction "25_25") (pintype "passive"))
    )
    (net (code "77") (name "/SD_VDD") (class "Default")
      (node (ref "C10") (pin "1") (pinfunction "1_1") (pintype "passive"))
      (node (ref "C11") (pin "1") (pinfunction "1_1") (pintype "passive"))
      (node (ref "L1") (pin "2") (pinfunction "2_2") (pintype "passive"))
      (node (ref "X1") (pin "VDD") (pinfunction "VDD_VDD") (pintype "passive"))
    )
    (net (code "78") (name "/SSI_ENC1_CLK") (class "Default")
      (node (ref "U6") (pin "7") (pinfunction "1Y_7") (pintype "output"))
      (node (ref "U7") (pin "15") (pinfunction "1D_15") (pintype "input"))
    )
    (net (code "79") (name "/SSI_ENC1_CLK+") (class "Default")
      (node (ref "J8") (pin "3") (pinfunction "3_3") (pintype "passive"))
      (node (ref "U7") (pin "14") (pinfunction "1Y_14") (pintype "output"))
    )
    (net (code "80") (name "/SSI_ENC1_CLK-") (class "Default")
      (node (ref "J8") (pin "4") (pinfunction "4_4") (pintype "passive"))
      (node (ref "U7") (pin "13") (pinfunction "1Z_13") (pintype "output"))
    )
    (net (code "81") (name "/SSI_ENC1_DATA+") (class "Default")
      (node (ref "J8") (pin "6") (pinfunction "6_6") (pintype "passive"))
      (node (ref "U7") (pin "2") (pinfunction "1A_2") (pintype "input"))
    )
    (net (code "82") (name "/SSI_ENC1_DATA-") (class "Default")
      (node (ref "J8") (pin "5") (pinfunction "5_5") (pintype "passive"))
      (node (ref "U7") (pin "1") (pinfunction "1B_1") (pintype "input"))
    )
    (net (code "83") (name "/SSI_ENC2_CLK") (class "Default")
      (node (ref "U6") (pin "3") (pinfunction "2Y_3") (pintype "output"))
      (node (ref "U7") (pin "9") (pinfunction "2D_9") (pintype "input"))
    )
    (net (code "84") (name "/SSI_ENC2_CLK+") (class "Default")
      (node (ref "J9") (pin "3") (pinfunction "3_3") (pintype "passive"))
      (node (ref "U7") (pin "10") (pinfunction "2Y_10") (pintype "output"))
    )
    (net (code "85") (name "/SSI_ENC2_CLK-") (class "Default")
      (node (ref "J9") (pin "4") (pinfunction "4_4") (pintype "passive"))
      (node (ref "U7") (pin "11") (pinfunction "2Z_11") (pintype "output"))
    )
    (net (code "86") (name "/SSI_ENC2_DATA+") (class "Default")
      (node (ref "J9") (pin "6") (pinfunction "6_6") (pintype "passive"))
      (node (ref "U7") (pin "6") (pinfunction "2A_6") (pintype "input"))
    )
    (net (code "87") (name "/SSI_ENC2_DATA-") (class "Default")
      (node (ref "J9") (pin "5") (pinfunction "5_5") (pintype "passive"))
      (node (ref "U7") (pin "7") (pinfunction "2B_7") (pintype "input"))
    )
    (net (code "88") (name "/USBDM") (class "Default")
      (node (ref "EXT1") (pin "1") (pinfunction "1_1") (pintype "passive"))
    )
    (net (code "89") (name "/USBDP") (class "Default")
      (node (ref "EXT1") (pin "3") (pinfunction "3_3") (pintype "passive"))
    )
    (net (code "90") (name "/VBAT") (class "Default")
      (node (ref "EXT1") (pin "23") (pinfunction "23_23") (pintype "passive"))
    )
    (net (code "91") (name "/XPC_RS-485_RXD0") (class "Default")
      (node (ref "J2") (pin "1") (pinfunction "1_1") (pintype "passive"))
      (node (ref "JP4") (pin "2") (pinfunction "2_2") (pintype "passive"))
      (node (ref "U2") (pin "14") (pinfunction "A_14") (pintype "input"))
    )
    (net (code "92") (name "/XPC_RS-485_RXD1") (class "Default")
      (node (ref "J2") (pin "2") (pinfunction "2_2") (pintype "passive"))
      (node (ref "R4") (pin "1") (pinfunction "1_1") (pintype "passive"))
      (node (ref "U2") (pin "13") (pinfunction "B_13") (pintype "input"))
    )
    (net (code "93") (name "/XPC_RS-485_TXD0") (class "Default")
      (node (ref "J2") (pin "5") (pinfunction "5_5") (pintype "passive"))
      (node (ref "JP3") (pin "2") (pinfunction "2_2") (pintype "passive"))
      (node (ref "U2") (pin "11") (pinfunction "Y_11") (pintype "output"))
    )
    (net (code "94") (name "/XPC_RS-485_TXD1") (class "Default")
      (node (ref "J2") (pin "4") (pinfunction "4_4") (pintype "passive"))
      (node (ref "R3") (pin "1") (pinfunction "1_1") (pintype "passive"))
      (node (ref "U2") (pin "12") (pinfunction "Z_12") (pintype "output"))
    )
    (net (code "95") (name "GND") (class "Default")
      (node (ref "C1") (pin "2") (pinfunction "2_2") (pintype "passive"))
      (node (ref "C10") (pin "2") (pinfunction "2_2") (pintype "passive"))
      (node (ref "C11") (pin "2") (pinfunction "2_2") (pintype "passive"))
      (node (ref "C12") (pin "2") (pinfunction "2_2") (pintype "passive"))
      (node (ref "C13") (pin "2") (pinfunction "2_2") (pintype "passive"))
      (node (ref "C14") (pin "2") (pinfunction "2_2") (pintype "passive"))
      (node (ref "C15") (pin "2") (pinfunction "2_2") (pintype "passive"))
      (node (ref "C16") (pin "2") (pinfunction "2_2") (pintype "passive"))
      (node (ref "C17") (pin "2") (pinfunction "2_2") (pintype "passive"))
      (node (ref "C18") (pin "2") (pinfunction "2_2") (pintype "passive"))
      (node (ref "C19") (pin "2") (pinfunction "2_2") (pintype "passive"))
      (node (ref "C2") (pin "2") (pinfunction "2_2") (pintype "passive"))
      (node (ref "C20") (pin "2") (pinfunction "2_2") (pintype "passive"))
      (node (ref "C21") (pin "2") (pinfunction "2_2") (pintype "passive"))
      (node (ref "C22") (pin "2") (pinfunction "2_2") (pintype "passive"))
      (node (ref "C23") (pin "2") (pinfunction "2_2") (pintype "passive"))
      (node (ref "C24") (pin "2") (pinfunction "2_2") (pintype "passive"))
      (node (ref "C25") (pin "2") (pinfunction "2_2") (pintype "passive"))
      (node (ref "C26") (pin "2") (pinfunction "2_2") (pintype "passive"))
      (node (ref "C27") (pin "2") (pinfunction "2_2") (pintype "passive"))
      (node (ref "C28") (pin "2") (pinfunction "2_2") (pintype "passive"))
      (node (ref "C29") (pin "2") (pinfunction "2_2") (pintype "passive"))
      (node (ref "C3") (pin "2") (pinfunction "2_2") (pintype "passive"))
      (node (ref "C30") (pin "2") (pinfunction "2_2") (pintype "passive"))
      (node (ref "C31") (pin "2") (pinfunction "2_2") (pintype "passive"))
      (node (ref "C32") (pin "2") (pinfunction "2_2") (pintype "passive"))
      (node (ref "C33") (pin "2") (pinfunction "2_2") (pintype "passive"))
      (node (ref "C34") (pin "2") (pinfunction "2_2") (pintype "passive"))
      (node (ref "C35") (pin "2") (pinfunction "2_2") (pintype "passive"))
      (node (ref "C36") (pin "2") (pinfunction "2_2") (pintype "passive"))
      (node (ref "C37") (pin "2") (pinfunction "2_2") (pintype "passive"))
      (node (ref "C38") (pin "2") (pinfunction "2_2") (pintype "passive"))
      (node (ref "C39") (pin "2") (pinfunction "2_2") (pintype "passive"))
      (node (ref "C4") (pin "2") (pinfunction "2_2") (pintype "passive"))
      (node (ref "C40") (pin "2") (pinfunction "2_2") (pintype "passive"))
      (node (ref "C41") (pin "2") (pinfunction "2_2") (pintype "passive"))
      (node (ref "C42") (pin "2") (pinfunction "2_2") (pintype "passive"))
      (node (ref "C43") (pin "2") (pinfunction "2_2") (pintype "passive"))
      (node (ref "C44") (pin "2") (pinfunction "2_2") (pintype "passive"))
      (node (ref "C45") (pin "2") (pinfunction "2_2") (pintype "passive"))
      (node (ref "C5") (pin "2") (pinfunction "2_2") (pintype "passive"))
      (node (ref "C6") (pin "2") (pinfunction "2_2") (pintype "passive"))
      (node (ref "C7") (pin "2") (pinfunction "2_2") (pintype "passive"))
      (node (ref "C8") (pin "2") (pinfunction "2_2") (pintype "passive"))
      (node (ref "C9") (pin "2") (pinfunction "2_2") (pintype "passive"))
      (node (ref "EXT1") (pin "6") (pinfunction "6_6") (pintype "passive"))
      (node (ref "EXT2") (pin "25") (pinfunction "25_25") (pintype "passive"))
      (node (ref "EXT2") (pin "3") (pinfunction "3_3") (pintype "passive"))
      (node (ref "EXT2") (pin "6") (pinfunction "6_6") (pintype "passive"))
      (node (ref "J1") (pin "8") (pinfunction "8_8") (pintype "passive"))
      (node (ref "J10") (pin "2") (pinfunction "S_2") (pintype "passive"))
      (node (ref "J11") (pin "2") (pinfunction "S_2") (pintype "passive"))
      (node (ref "J12") (pin "2") (pinfunction "S_2") (pintype "passive"))
      (node (ref "J13") (pin "2") (pinfunction "S_2") (pintype "passive"))
      (node (ref "J14") (pin "2") (pinfunction "S_2") (pintype "passive"))
      (node (ref "J15") (pin "2") (pinfunction "S_2") (pintype "passive"))
      (node (ref "J16") (pin "2") (pinfunction "S_2") (pintype "passive"))
      (node (ref "J2") (pin "8") (pinfunction "8_8") (pintype "passive"))
      (node (ref "J3") (pin "4") (pinfunction "S_4") (pintype "passive"))
      (node (ref "J4") (pin "4") (pinfunction "S_4") (pintype "passive"))
      (node (ref "J5") (pin "4") (pinfunction "S_4") (pintype "passive"))
      (node (ref "J7") (pin "7") (pinfunction "7_7") (pintype "passive"))
      (node (ref "J7") (pin "8") (pinfunction "8_8") (pintype "passive"))
      (node (ref "J8") (pin "2") (pinfunction "2_2") (pintype "passive"))
      (node (ref "J9") (pin "2") (pinfunction "2_2") (pintype "passive"))
      (node (ref "PS1") (pin "2") (pinfunction "S_2") (pintype "passive"))
      (node (ref "Q3") (pin "2") (pinfunction "E_2") (pintype "passive"))
      (node (ref "R10") (pin "1") (pinfunction "1_1") (pintype "passive"))
      (node (ref "R19") (pin "1") (pinfunction "1_1") (pintype "passive"))
      (node (ref "R26") (pin "1") (pinfunction "1_1") (pintype "passive"))
      (node (ref "R36") (pin "1") (pinfunction "1_1") (pintype "passive"))
      (node (ref "R44") (pin "1") (pinfunction "1_1") (pintype "passive"))
      (node (ref "R52") (pin "1") (pinfunction "1_1") (pintype "passive"))
      (node (ref "R60") (pin "1") (pinfunction "1_1") (pintype "passive"))
      (node (ref "S3") (pin "1") (pinfunction "1_1") (pintype "passive"))
      (node (ref "S4") (pin "1") (pinfunction "1_1") (pintype "passive"))
      (node (ref "U1") (pin "10") (pinfunction "GND_2_10") (pintype "passive"))
      (node (ref "U1") (pin "15") (pinfunction "GND_2_3_15") (pintype "passive"))
      (node (ref "U1") (pin "2") (pinfunction "GND_1_2_2") (pintype "passive"))
      (node (ref "U1") (pin "7") (pinfunction "GND_1_7") (pintype "passive"))
      (node (ref "U1") (pin "8") (pinfunction "GND_1_3_8") (pintype "passive"))
      (node (ref "U1") (pin "9") (pinfunction "GND_2_2_9") (pintype "passive"))
      (node (ref "U10") (pin "11") (pinfunction "FSYNC_11") (pintype "input"))
      (node (ref "U10") (pin "18") (pinfunction "GND_18") (pintype "power_in"))
      (node (ref "U10") (pin "20") (pinfunction "GND_20") (pintype "power_in"))
      (node (ref "U11") (pin "7") (pinfunction "VEE_7") (pintype "power_in"))
      (node (ref "U11") (pin "8") (pinfunction "GND_8") (pintype "power_in"))
      (node (ref "U12") (pin "10") (pinfunction "Y1_10") (pintype "bidirectional"))
      (node (ref "U12") (pin "11") (pinfunction "Z0_11") (pintype "bidirectional"))
      (node (ref "U12") (pin "12") (pinfunction "Z1_12") (pintype "bidirectional"))
      (node (ref "U12") (pin "6") (pinfunction "Y0_6") (pintype "bidirectional"))
      (node (ref "U12") (pin "7") (pinfunction "VEE_7") (pintype "power_in"))
      (node (ref "U12") (pin "8") (pinfunction "GND_8") (pintype "power_in"))
      (node (ref "U13") (pin "11") (pinfunction "FSYNC_11") (pintype "input"))
      (node (ref "U13") (pin "18") (pinfunction "GND_18") (pintype "power_in"))
      (node (ref "U13") (pin "20") (pinfunction "GND_20") (pintype "power_in"))
      (node (ref "U2") (pin "10") (pinfunction "GND_2_10") (pintype "passive"))
      (node (ref "U2") (pin "15") (pinfunction "GND_2_3_15") (pintype "passive"))
      (node (ref "U2") (pin "2") (pinfunction "GND_1_2_2") (pintype "passive"))
      (node (ref "U2") (pin "7") (pinfunction "GND_1_7") (pintype "passive"))
      (node (ref "U2") (pin "8") (pinfunction "GND_1_3_8") (pintype "passive"))
      (node (ref "U2") (pin "9") (pinfunction "GND_2_2_9") (pintype "passive"))
      (node (ref "U3") (pin "12") (pinfunction "~{G}_12") (pintype "input"))
      (node (ref "U3") (pin "8") (pinfunction "GND_8") (pintype "passive"))
      (node (ref "U4") (pin "15") (pinfunction "G_15") (pintype "input"))
      (node (ref "U4") (pin "8") (pinfunction "GND_8") (pintype "power_in"))
      (node (ref "U5") (pin "10") (pinfunction "3B_10") (pintype "input"))
      (node (ref "U5") (pin "11") (pinfunction "3A_11") (pintype "input"))
      (node (ref "U5") (pin "13") (pinfunction "4B_13") (pintype "input"))
      (node (ref "U5") (pin "14") (pinfunction "4A_14") (pintype "input"))
      (node (ref "U5") (pin "15") (pinfunction "G_15") (pintype "input"))
      (node (ref "U5") (pin "8") (pinfunction "GND_8") (pintype "power_in"))
      (node (ref "U6") (pin "4") (pinfunction "GND_4") (pintype "passive"))
      (node (ref "U7") (pin "8") (pinfunction "GND_8") (pintype "passive"))
      (node (ref "U8") (pin "4") (pinfunction "GND_4") (pintype "passive"))
      (node (ref "U9") (pin "3") (pinfunction "GND_3") (pintype "passive"))
      (node (ref "X1") (pin "GND1") (pinfunction "GND_GND1") (pintype "passive"))
      (node (ref "X1") (pin "GND2") (pinfunction "GND_GND2") (pintype "passive"))
      (node (ref "X1") (pin "GND3") (pinfunction "GND_GND3") (pintype "passive"))
      (node (ref "X1") (pin "VSS") (pinfunction "VSS_VSS") (pintype "passive"))
    )
    (net (code "96") (name "Net-(C15-Pad1)") (class "Default")
      (node (ref "C15") (pin "1") (pinfunction "1_1") (pintype "passive"))
      (node (ref "R16") (pin "2") (pinfunction "2_2") (pintype "passive"))
      (node (ref "R17") (pin "1") (pinfunction "1_1") (pintype "passive"))
    )
    (net (code "97") (name "Net-(C17-Pad1)") (class "Default")
      (node (ref "C17") (pin "1") (pinfunction "1_1") (pintype "passive"))
      (node (ref "R20") (pin "2") (pinfunction "2_2") (pintype "passive"))
      (node (ref "R21") (pin "1") (pinfunction "1_1") (pintype "passive"))
    )
    (net (code "98") (name "Net-(C19-Pad1)") (class "Default")
      (node (ref "C19") (pin "1") (pinfunction "1_1") (pintype "passive"))
      (node (ref "R23") (pin "2") (pinfunction "2_2") (pintype "passive"))
      (node (ref "R24") (pin "1") (pinfunction "1_1") (pintype "passive"))
    )
    (net (code "99") (name "Net-(C21-Pad1)") (class "Default")
      (node (ref "C21") (pin "1") (pinfunction "1_1") (pintype "passive"))
      (node (ref "R27") (pin "2") (pinfunction "2_2") (pintype "passive"))
      (node (ref "R28") (pin "1") (pinfunction "1_1") (pintype "passive"))
    )
    (net (code "100") (name "Net-(C23-Pad1)") (class "Default")
      (node (ref "C23") (pin "1") (pinfunction "1_1") (pintype "passive"))
      (node (ref "R30") (pin "2") (pinfunction "2_2") (pintype "passive"))
      (node (ref "R31") (pin "1") (pinfunction "1_1") (pintype "passive"))
    )
    (net (code "101") (name "Net-(C25-Pad1)") (class "Default")
      (node (ref "C25") (pin "1") (pinfunction "1_1") (pintype "passive"))
      (node (ref "R34") (pin "2") (pinfunction "2_2") (pintype "passive"))
      (node (ref "R35") (pin "1") (pinfunction "1_1") (pintype "passive"))
    )
    (net (code "102") (name "Net-(C27-Pad1)") (class "Default")
      (node (ref "C27") (pin "1") (pinfunction "1_1") (pintype "passive"))
      (node (ref "R38") (pin "2") (pinfunction "2_2") (pintype "passive"))
      (node (ref "R39") (pin "1") (pinfunction "1_1") (pintype "passive"))
    )
    (net (code "103") (name "Net-(C29-Pad1)") (class "Default")
      (node (ref "C29") (pin "1") (pinfunction "1_1") (pintype "passive"))
      (node (ref "R42") (pin "2") (pinfunction "2_2") (pintype "passive"))
      (node (ref "R43") (pin "1") (pinfunction "1_1") (pintype "passive"))
    )
    (net (code "104") (name "Net-(C32-Pad1)") (class "Default")
      (node (ref "C32") (pin "1") (pinfunction "1_1") (pintype "passive"))
      (node (ref "R46") (pin "2") (pinfunction "2_2") (pintype "passive"))
      (node (ref "R47") (pin "1") (pinfunction "1_1") (pintype "passive"))
    )
    (net (code "105") (name "Net-(C34-Pad1)") (class "Default")
      (node (ref "C34") (pin "1") (pinfunction "1_1") (pintype "passive"))
      (node (ref "R50") (pin "2") (pinfunction "2_2") (pintype "passive"))
      (node (ref "R51") (pin "1") (pinfunction "1_1") (pintype "passive"))
    )
    (net (code "106") (name "Net-(C36-Pad1)") (class "Default")
      (node (ref "C36") (pin "1") (pinfunction "1_1") (pintype "passive"))
      (node (ref "R54") (pin "2") (pinfunction "2_2") (pintype "passive"))
      (node (ref "R55") (pin "1") (pinfunction "1_1") (pintype "passive"))
    )
    (net (code "107") (name "Net-(C38-Pad1)") (class "Default")
      (node (ref "C38") (pin "1") (pinfunction "1_1") (pintype "passive"))
      (node (ref "R58") (pin "2") (pinfunction "2_2") (pintype "passive"))
      (node (ref "R59") (pin "1") (pinfunction "1_1") (pintype "passive"))
    )
    (net (code "108") (name "Net-(J10A-S)") (class "Default")
      (node (ref "J10") (pin "1") (pinfunction "S_1") (pintype "passive"))
      (node (ref "R18") (pin "1") (pinfunction "1_1") (pintype "passive"))
    )
    (net (code "109") (name "Net-(J11A-S)") (class "Default")
      (node (ref "J11") (pin "1") (pinfunction "S_1") (pintype "passive"))
      (node (ref "R25") (pin "1") (pinfunction "1_1") (pintype "passive"))
    )
    (net (code "110") (name "Net-(J12A-S)") (class "Default")
      (node (ref "J12") (pin "1") (pinfunction "S_1") (pintype "passive"))
      (node (ref "R32") (pin "1") (pinfunction "1_1") (pintype "passive"))
    )
    (net (code "111") (name "Net-(J13A-S)") (class "Default")
      (node (ref "J13") (pin "1") (pinfunction "S_1") (pintype "passive"))
      (node (ref "R40") (pin "1") (pinfunction "1_1") (pintype "passive"))
    )
    (net (code "112") (name "Net-(J14A-S)") (class "Default")
      (node (ref "J14") (pin "1") (pinfunction "S_1") (pintype "passive"))
      (node (ref "R48") (pin "1") (pinfunction "1_1") (pintype "passive"))
    )
    (net (code "113") (name "Net-(J15A-S)") (class "Default")
      (node (ref "J15") (pin "1") (pinfunction "S_1") (pintype "passive"))
      (node (ref "R56") (pin "1") (pinfunction "1_1") (pintype "passive"))
    )
    (net (code "114") (name "Net-(JP1-Pad1)") (class "Default")
      (node (ref "JP1") (pin "1") (pinfunction "1_1") (pintype "passive"))
      (node (ref "R1") (pin "2") (pinfunction "2_2") (pintype "passive"))
    )
    (net (code "115") (name "Net-(JP2-Pad1)") (class "Default")
      (node (ref "JP2") (pin "1") (pinfunction "1_1") (pintype "passive"))
      (node (ref "R2") (pin "2") (pinfunction "2_2") (pintype "passive"))
    )
    (net (code "116") (name "Net-(JP3-Pad1)") (class "Default")
      (node (ref "JP3") (pin "1") (pinfunction "1_1") (pintype "passive"))
      (node (ref "R3") (pin "2") (pinfunction "2_2") (pintype "passive"))
    )
    (net (code "117") (name "Net-(JP4-Pad1)") (class "Default")
      (node (ref "JP4") (pin "1") (pinfunction "1_1") (pintype "passive"))
      (node (ref "R4") (pin "2") (pinfunction "2_2") (pintype "passive"))
    )
    (net (code "118") (name "Net-(Q1-B)") (class "Default")
      (node (ref "Q1") (pin "1") (pinfunction "B_1") (pintype "passive"))
      (node (ref "R5") (pin "1") (pinfunction "1_1") (pintype "passive"))
      (node (ref "R6") (pin "2") (pinfunction "2_2") (pintype "passive"))
    )
    (net (code "119") (name "Net-(Q2-PadB)") (class "Default")
      (node (ref "Q2") (pin "B") (pinfunction "B_B") (pintype "passive"))
      (node (ref "R7") (pin "1") (pinfunction "1_1") (pintype "passive"))
      (node (ref "R8") (pin "2") (pinfunction "2_2") (pintype "passive"))
    )
    (net (code "120") (name "Net-(Q3-B)") (class "Default")
      (node (ref "Q3") (pin "1") (pinfunction "B_1") (pintype "passive"))
      (node (ref "R10") (pin "2") (pinfunction "2_2") (pintype "passive"))
      (node (ref "R9") (pin "2") (pinfunction "2_2") (pintype "passive"))
    )
    (net (code "121") (name "Net-(Q3-C)") (class "Default")
      (node (ref "Q3") (pin "3") (pinfunction "C_3") (pintype "passive"))
      (node (ref "R8") (pin "1") (pinfunction "1_1") (pintype "passive"))
    )
    (net (code "122") (name "Net-(R15-Pad1)") (class "Default")
      (node (ref "R15") (pin "1") (pinfunction "1_1") (pintype "passive"))
      (node (ref "R16") (pin "1") (pinfunction "1_1") (pintype "passive"))
      (node (ref "R18") (pin "2") (pinfunction "2_2") (pintype "passive"))
      (node (ref "R19") (pin "2") (pinfunction "2_2") (pintype "passive"))
      (node (ref "R20") (pin "1") (pinfunction "1_1") (pintype "passive"))
    )
    (net (code "123") (name "Net-(R22-Pad1)") (class "Default")
      (node (ref "R22") (pin "1") (pinfunction "1_1") (pintype "passive"))
      (node (ref "R23") (pin "1") (pinfunction "1_1") (pintype "passive"))
      (node (ref "R25") (pin "2") (pinfunction "2_2") (pintype "passive"))
      (node (ref "R26") (pin "2") (pinfunction "2_2") (pintype "passive"))
      (node (ref "R27") (pin "1") (pinfunction "1_1") (pintype "passive"))
    )
    (net (code "124") (name "Net-(R29-Pad1)") (class "Default")
      (node (ref "R29") (pin "1") (pinfunction "1_1") (pintype "passive"))
      (node (ref "R30") (pin "1") (pinfunction "1_1") (pintype "passive"))
      (node (ref "R32") (pin "2") (pinfunction "2_2") (pintype "passive"))
      (node (ref "R33") (pin "2") (pinfunction "2_2") (pintype "passive"))
      (node (ref "R34") (pin "1") (pinfunction "1_1") (pintype "passive"))
    )
    (net (code "125") (name "Net-(R33-Pad1)") (class "Default")
      (node (ref "R33") (pin "1") (pinfunction "1_1") (pintype "passive"))
      (node (ref "R36") (pin "2") (pinfunction "2_2") (pintype "passive"))
    )
    (net (code "126") (name "Net-(R37-Pad1)") (class "Default")
      (node (ref "R37") (pin "1") (pinfunction "1_1") (pintype "passive"))
      (node (ref "R38") (pin "1") (pinfunction "1_1") (pintype "passive"))
      (node (ref "R40") (pin "2") (pinfunction "2_2") (pintype "passive"))
      (node (ref "R41") (pin "2") (pinfunction "2_2") (pintype "passive"))
      (node (ref "R42") (pin "1") (pinfunction "1_1") (pintype "passive"))
    )
    (net (code "127") (name "Net-(R41-Pad1)") (class "Default")
      (node (ref "R41") (pin "1") (pinfunction "1_1") (pintype "passive"))
      (node (ref "R44") (pin "2") (pinfunction "2_2") (pintype "passive"))
    )
    (net (code "128") (name "Net-(R45-Pad1)") (class "Default")
      (node (ref "R45") (pin "1") (pinfunction "1_1") (pintype "passive"))
      (node (ref "R46") (pin "1") (pinfunction "1_1") (pintype "passive"))
      (node (ref "R48") (pin "2") (pinfunction "2_2") (pintype "passive"))
      (node (ref "R49") (pin "2") (pinfunction "2_2") (pintype "passive"))
      (node (ref "R50") (pin "1") (pinfunction "1_1") (pintype "passive"))
    )
    (net (code "129") (name "Net-(R49-Pad1)") (class "Default")
      (node (ref "R49") (pin "1") (pinfunction "1_1") (pintype "passive"))
      (node (ref "R52") (pin "2") (pinfunction "2_2") (pintype "passive"))
    )
    (net (code "130") (name "Net-(R53-Pad1)") (class "Default")
      (node (ref "R53") (pin "1") (pinfunction "1_1") (pintype "passive"))
      (node (ref "R54") (pin "1") (pinfunction "1_1") (pintype "passive"))
      (node (ref "R56") (pin "2") (pinfunction "2_2") (pintype "passive"))
      (node (ref "R57") (pin "2") (pinfunction "2_2") (pintype "passive"))
      (node (ref "R58") (pin "1") (pinfunction "1_1") (pintype "passive"))
    )
    (net (code "131") (name "Net-(R57-Pad1)") (class "Default")
      (node (ref "R57") (pin "1") (pinfunction "1_1") (pintype "passive"))
      (node (ref "R60") (pin "2") (pinfunction "2_2") (pintype "passive"))
    )
    (net (code "132") (name "Net-(U3-1A)") (class "Default")
      (node (ref "J6") (pin "1") (pinfunction "1_1") (pintype "passive"))
      (node (ref "U3") (pin "2") (pinfunction "1A_2") (pintype "input"))
    )
    (net (code "133") (name "Net-(U3-1B)") (class "Default")
      (node (ref "J6") (pin "2") (pinfunction "2_2") (pintype "passive"))
      (node (ref "U3") (pin "1") (pinfunction "1B_1") (pintype "input"))
    )
    (net (code "134") (name "Net-(U3-2A)") (class "Default")
      (node (ref "J6") (pin "3") (pinfunction "3_3") (pintype "passive"))
      (node (ref "U3") (pin "6") (pinfunction "2A_6") (pintype "input"))
    )
    (net (code "135") (name "Net-(U3-2B)") (class "Default")
      (node (ref "J6") (pin "4") (pinfunction "4_4") (pintype "passive"))
      (node (ref "U3") (pin "7") (pinfunction "2B_7") (pintype "input"))
    )
    (net (code "136") (name "Net-(U3-3A)") (class "Default")
      (node (ref "J6") (pin "5") (pinfunction "5_5") (pintype "passive"))
      (node (ref "U3") (pin "10") (pinfunction "3A_10") (pintype "input"))
    )
    (net (code "137") (name "Net-(U3-3B)") (class "Default")
      (node (ref "J6") (pin "6") (pinfunction "6_6") (pintype "passive"))
      (node (ref "U3") (pin "9") (pinfunction "3B_9") (pintype "input"))
    )
    (net (code "138") (name "Net-(U3-4A)") (class "Default")
      (node (ref "J6") (pin "7") (pinfunction "7_7") (pintype "passive"))
      (node (ref "U3") (pin "14") (pinfunction "4A_14") (pintype "input"))
    )
    (net (code "139") (name "Net-(U3-4B)") (class "Default")
      (node (ref "J6") (pin "8") (pinfunction "8_8") (pintype "passive"))
      (node (ref "U3") (pin "15") (pinfunction "4B_15") (pintype "input"))
    )
    (net (code "140") (name "Net-(U4A-~{A}{slash}B)") (class "Default")
      (node (ref "S3") (pin "2") (pinfunction "2_2") (pintype "passive"))
      (node (ref "U4") (pin "1") (pinfunction "~{A}/B_1") (pintype "input"))
      (node (ref "U5") (pin "1") (pinfunction "~{A}/B_1") (pintype "input"))
    )
    (net (code "141") (name "Net-(U9-Y)") (class "Default")
      (node (ref "R6") (pin "1") (pinfunction "1_1") (pintype "passive"))
      (node (ref "U9") (pin "4") (pinfunction "Y_4") (pintype "output"))
    )
    (net (code "142") (name "Net-(U10-REGOUT)") (class "Default")
      (node (ref "C6") (pin "1") (pinfunction "1_1") (pintype "passive"))
      (node (ref "U10") (pin "10") (pinfunction "REGOUT_10") (pintype "input"))
    )
    (net (code "143") (name "Net-(U11A-W0)") (class "Default")
      (node (ref "C16") (pin "1") (pinfunction "1_1") (pintype "passive"))
      (node (ref "R17") (pin "2") (pinfunction "2_2") (pintype "passive"))
      (node (ref "U11") (pin "15") (pinfunction "W0_15") (pintype "bidirectional"))
    )
    (net (code "144") (name "Net-(U11A-W1)") (class "Default")
      (node (ref "C18") (pin "1") (pinfunction "1_1") (pintype "passive"))
      (node (ref "R21") (pin "2") (pinfunction "2_2") (pintype "passive"))
      (node (ref "U11") (pin "1") (pinfunction "W1_1") (pintype "bidirectional"))
    )
    (net (code "145") (name "Net-(U11A-X0)") (class "Default")
      (node (ref "C20") (pin "1") (pinfunction "1_1") (pintype "passive"))
      (node (ref "R24") (pin "2") (pinfunction "2_2") (pintype "passive"))
      (node (ref "U11") (pin "2") (pinfunction "X0_2") (pintype "bidirectional"))
    )
    (net (code "146") (name "Net-(U11A-X1)") (class "Default")
      (node (ref "C22") (pin "1") (pinfunction "1_1") (pintype "passive"))
      (node (ref "R28") (pin "2") (pinfunction "2_2") (pintype "passive"))
      (node (ref "U11") (pin "3") (pinfunction "X1_3") (pintype "bidirectional"))
    )
    (net (code "147") (name "Net-(U11A-Y0)") (class "Default")
      (node (ref "C24") (pin "1") (pinfunction "1_1") (pintype "passive"))
      (node (ref "R31") (pin "2") (pinfunction "2_2") (pintype "passive"))
      (node (ref "U11") (pin "6") (pinfunction "Y0_6") (pintype "bidirectional"))
    )
    (net (code "148") (name "Net-(U11A-Y1)") (class "Default")
      (node (ref "C26") (pin "1") (pinfunction "1_1") (pintype "passive"))
      (node (ref "R35") (pin "2") (pinfunction "2_2") (pintype "passive"))
      (node (ref "U11") (pin "10") (pinfunction "Y1_10") (pintype "bidirectional"))
    )
    (net (code "149") (name "Net-(U11A-Z0)") (class "Default")
      (node (ref "C28") (pin "1") (pinfunction "1_1") (pintype "passive"))
      (node (ref "R39") (pin "2") (pinfunction "2_2") (pintype "passive"))
      (node (ref "U11") (pin "11") (pinfunction "Z0_11") (pintype "bidirectional"))
    )
    (net (code "150") (name "Net-(U11A-Z1)") (class "Default")
      (node (ref "C30") (pin "1") (pinfunction "1_1") (pintype "passive"))
      (node (ref "R43") (pin "2") (pinfunction "2_2") (pintype "passive"))
      (node (ref "U11") (pin "12") (pinfunction "Z1_12") (pintype "bidirectional"))
    )
    (net (code "151") (name "Net-(U12A-W0)") (class "Default")
      (node (ref "C33") (pin "1") (pinfunction "1_1") (pintype "passive"))
      (node (ref "R47") (pin "2") (pinfunction "2_2") (pintype "passive"))
      (node (ref "U12") (pin "15") (pinfunction "W0_15") (pintype "bidirectional"))
    )
    (net (code "152") (name "Net-(U12A-W1)") (class "Default")
      (node (ref "C35") (pin "1") (pinfunction "1_1") (pintype "passive"))
      (node (ref "R51") (pin "2") (pinfunction "2_2") (pintype "passive"))
      (node (ref "U12") (pin "1") (pinfunction "W1_1") (pintype "bidirectional"))
    )
    (net (code "153") (name "Net-(U12A-X0)") (class "Default")
      (node (ref "C37") (pin "1") (pinfunction "1_1") (pintype "passive"))
      (node (ref "R55") (pin "2") (pinfunction "2_2") (pintype "passive"))
      (node (ref "U12") (pin "2") (pinfunction "X0_2") (pintype "bidirectional"))
    )
    (net (code "154") (name "Net-(U12A-X1)") (class "Default")
      (node (ref "C39") (pin "1") (pinfunction "1_1") (pintype "passive"))
      (node (ref "R59") (pin "2") (pinfunction "2_2") (pintype "passive"))
      (node (ref "U12") (pin "3") (pinfunction "X1_3") (pintype "bidirectional"))
    )
    (net (code "155") (name "Net-(U13-REGOUT)") (class "Default")
      (node (ref "C41") (pin "1") (pinfunction "1_1") (pintype "passive"))
      (node (ref "U13") (pin "10") (pinfunction "REGOUT_10") (pintype "input"))
    )
    (net (code "156") (name "unconnected-(J1-Pad3)") (class "Default")
      (node (ref "J1") (pin "3") (pinfunction "3_3") (pintype "passive"))
    )
    (net (code "157") (name "unconnected-(J1-Pad6)") (class "Default")
      (node (ref "J1") (pin "6") (pinfunction "6_6") (pintype "passive"))
    )
    (net (code "158") (name "unconnected-(J1-S1-PadS@1)") (class "Default")
      (node (ref "J1") (pin "S@1") (pinfunction "S1_S@1") (pintype "passive"))
    )
    (net (code "159") (name "unconnected-(J1-S2-PadS@2)") (class "Default")
      (node (ref "J1") (pin "S@2") (pinfunction "S2_S@2") (pintype "passive"))
    )
    (net (code "160") (name "unconnected-(J2-Pad3)") (class "Default")
      (node (ref "J2") (pin "3") (pinfunction "3_3") (pintype "passive"))
    )
    (net (code "161") (name "unconnected-(J2-Pad6)") (class "Default")
      (node (ref "J2") (pin "6") (pinfunction "6_6") (pintype "passive"))
    )
    (net (code "162") (name "unconnected-(J2-S1-PadS@1)") (class "Default")
      (node (ref "J2") (pin "S@1") (pinfunction "S1_S@1") (pintype "passive"))
    )
    (net (code "163") (name "unconnected-(J2-S2-PadS@2)") (class "Default")
      (node (ref "J2") (pin "S@2") (pinfunction "S2_S@2") (pintype "passive"))
    )
    (net (code "164") (name "unconnected-(U5A-3Y-Pad9)") (class "Default")
      (node (ref "U5") (pin "9") (pinfunction "3Y_9") (pintype "output"))
    )
    (net (code "165") (name "unconnected-(U5A-4Y-Pad12)") (class "Default")
      (node (ref "U5") (pin "12") (pinfunction "4Y_12") (pintype "output"))
    )
    (net (code "166") (name "unconnected-(U9-NC-Pad1)") (class "Default")
      (node (ref "U9") (pin "1") (pinfunction "NC_1") (pintype "no_connect"))
    )
    (net (code "167") (name "unconnected-(U10-AUX_CL-Pad7)") (class "Default")
      (node (ref "U10") (pin "7") (pinfunction "AUX_CL_7") (pintype "output"))
    )
    (net (code "168") (name "unconnected-(U10-AUX_DA-Pad21)") (class "Default")
      (node (ref "U10") (pin "21") (pinfunction "AUX_DA_21") (pintype "bidirectional"))
    )
    (net (code "169") (name "unconnected-(U12A-Y-Pad5)") (class "Default")
      (node (ref "U12") (pin "5") (pinfunction "Y_5") (pintype "bidirectional"))
    )
    (net (code "170") (name "unconnected-(U12A-Z-Pad13)") (class "Default")
      (node (ref "U12") (pin "13") (pinfunction "Z_13") (pintype "bidirectional"))
    )
    (net (code "171") (name "unconnected-(U13-AUX_CL-Pad7)") (class "Default")
      (node (ref "U13") (pin "7") (pinfunction "AUX_CL_7") (pintype "output"))
    )
    (net (code "172") (name "unconnected-(U13-AUX_DA-Pad21)") (class "Default")
      (node (ref "U13") (pin "21") (pinfunction "AUX_DA_21") (pintype "bidirectional"))
    )
  )
)
